# Elec_2013_Combined_v2.net
KiCad netlist of a schematic drawn in EAGLE
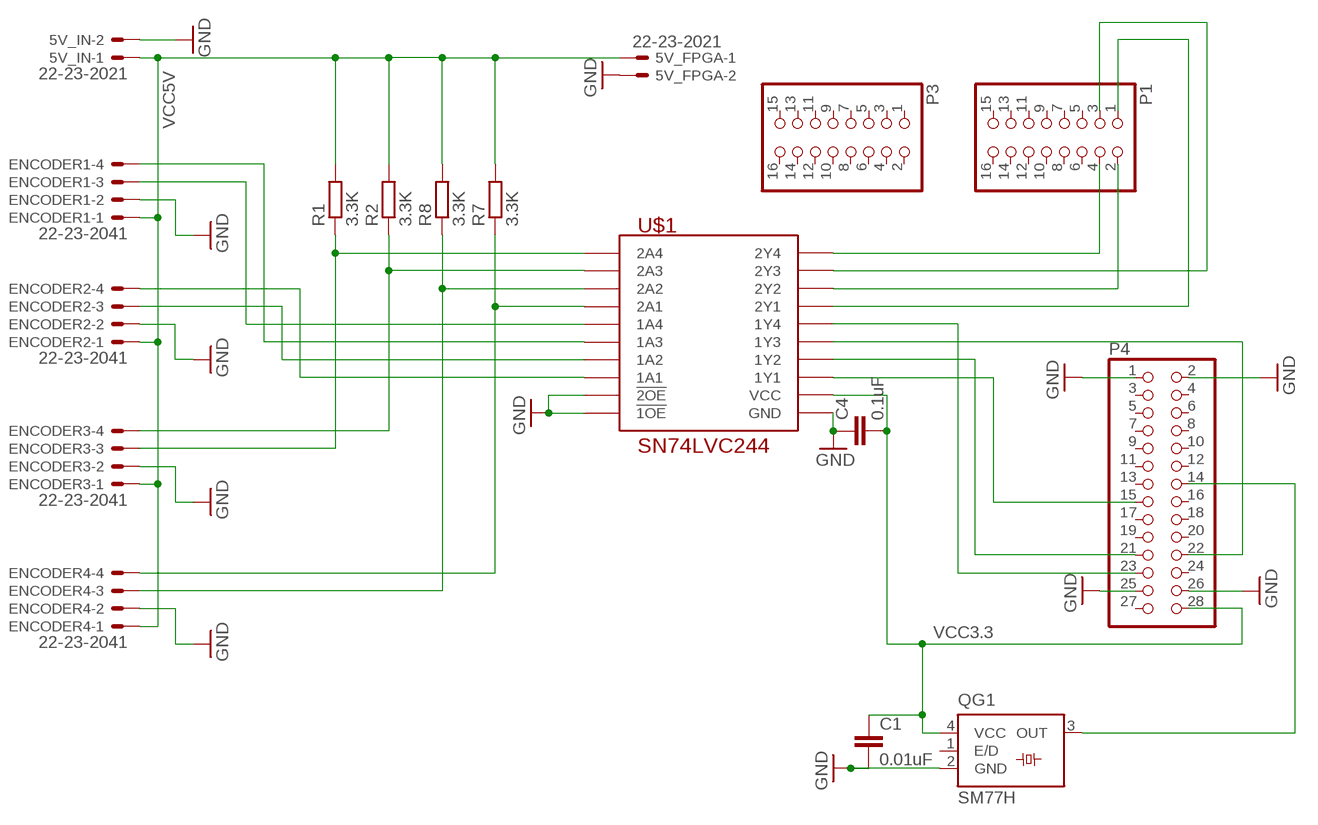
[diagram p0: schematic, sheet 1, part 1 of 2]
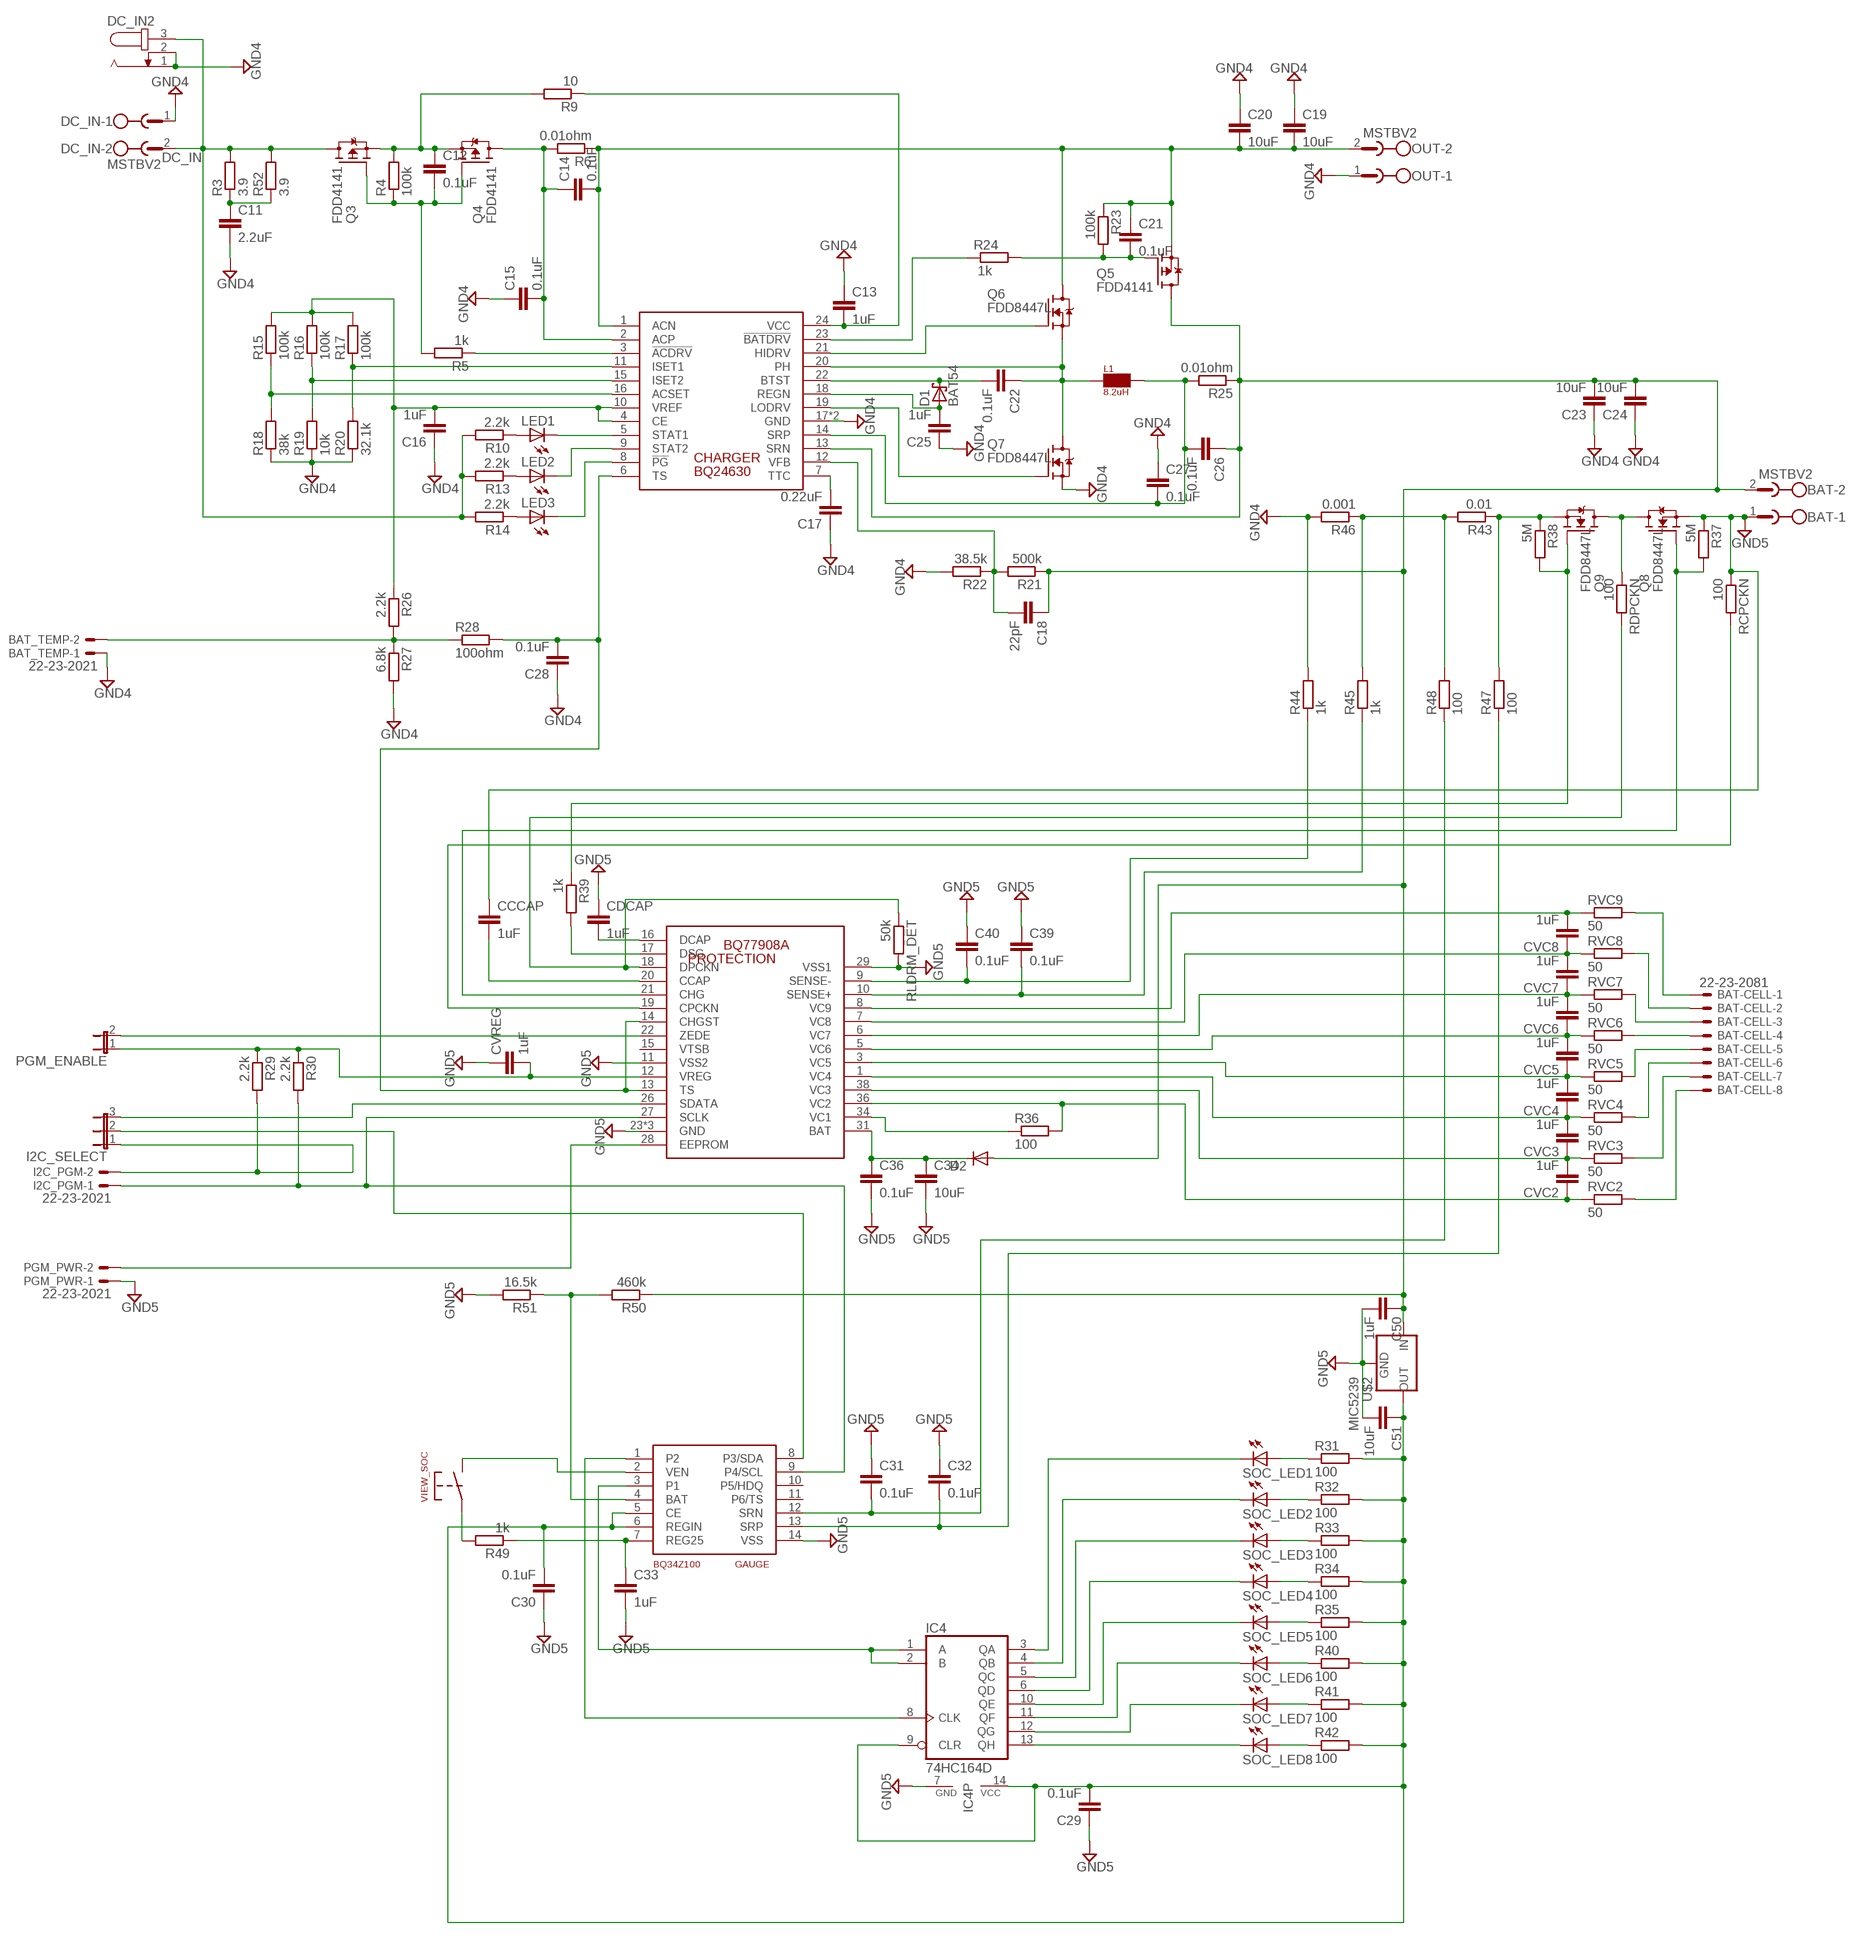
[diagram p1: schematic, sheet 1, part 2 of 2]

(export (version "E")
  (design (tool "Eeschema 10.0.6"))
  (components
    (comp (ref "5V_FPGA")
      (value "22-23-2021")
      (footprint "eagle-import:22-23-2021")
      (fields
        (field (name "MF") "MOLEX")
        (field (name "MF_1") "MOLEX")
        (field (name "MPN") "22-23-2021")
        (field (name "OC_FARNELL") "1462926")
        (field (name "OC_NEWARK") "25C3832")
      )
      (libsource (lib "eagle-import") (part "22-23-2021"))
    )
    (comp (ref "5V_IN")
      (value "22-23-2021")
      (footprint "eagle-import:22-23-2021")
      (fields (field (name "MF") "MOLEX"))
      (libsource (lib "eagle-import") (part "22-23-2021"))
    )
    (comp (ref "BAT")
      (value "MSTBV2")
      (footprint "eagle-import:MSTBV2")
      (fields
        (field (name "MPN") "MSTBV 2,5/2-GF-5.08")
        (field (name "MPN_1") "MSTBV 2,5/2-GF-5.08")
        (field (name "OC_FARNELL") "1792792")
        (field (name "OC_NEWARK") "69R9845")
      )
      (libsource (lib "eagle-import") (part "MSTBV2"))
    )
    (comp (ref "BAT-CELL")
      (value "22-23-2081")
      (footprint "eagle-import:22-23-2081")
      (fields (field (name "MF") "MOLEX"))
      (libsource (lib "eagle-import") (part "22-23-2081"))
    )
    (comp (ref "BAT_TEMP")
      (value "22-23-2021")
      (footprint "eagle-import:22-23-2021")
      (fields
        (field (name "MF") "MOLEX")
        (field (name "MF_1") "MOLEX")
        (field (name "MPN") "22-23-2021")
        (field (name "OC_FARNELL") "1462926")
        (field (name "OC_NEWARK") "25C3832")
      )
      (libsource (lib "eagle-import") (part "22-23-2021"))
    )
    (comp (ref "C1")
      (value "0.01uF")
      (footprint "eagle-import:C0603")
      (libsource (lib "eagle-import") (part "C-EUC0603"))
    )
    (comp (ref "C4")
      (value "0.1uF")
      (footprint "eagle-import:C0603")
      (libsource (lib "eagle-import") (part "C-EUC0603"))
    )
    (comp (ref "C11")
      (value "2.2uF")
      (footprint "eagle-import:C1206")
      (libsource (lib "eagle-import") (part "C-EUC1206"))
    )
    (comp (ref "C12")
      (value "0.1uF")
      (footprint "eagle-import:C0603")
      (libsource (lib "eagle-import") (part "C-EUC0603"))
    )
    (comp (ref "C13")
      (value "1uF")
      (footprint "eagle-import:C1206")
      (libsource (lib "eagle-import") (part "C-EUC1206"))
    )
    (comp (ref "C14")
      (value "0.1uF")
      (footprint "eagle-import:C0603")
      (libsource (lib "eagle-import") (part "C-EUC0603"))
    )
    (comp (ref "C15")
      (value "0.1uF")
      (footprint "eagle-import:C0603")
      (libsource (lib "eagle-import") (part "C-EUC0603"))
    )
    (comp (ref "C16")
      (value "1uF")
      (footprint "eagle-import:C0805")
      (libsource (lib "eagle-import") (part "C-EUC0805"))
    )
    (comp (ref "C17")
      (value "0.22uF")
      (footprint "eagle-import:C0603")
      (libsource (lib "eagle-import") (part "C-EUC0603"))
    )
    (comp (ref "C18")
      (value "22pF")
      (footprint "eagle-import:C0603")
      (libsource (lib "eagle-import") (part "C-EUC0603"))
    )
    (comp (ref "C19")
      (value "10uF")
      (footprint "eagle-import:C1812")
      (libsource (lib "eagle-import") (part "C-EUC1812"))
    )
    (comp (ref "C20")
      (value "10uF")
      (footprint "eagle-import:C1812")
      (libsource (lib "eagle-import") (part "C-EUC1812"))
    )
    (comp (ref "C21")
      (value "0.1uF")
      (footprint "eagle-import:C0603")
      (libsource (lib "eagle-import") (part "C-EUC0603"))
    )
    (comp (ref "C22")
      (value "0.1uF")
      (footprint "eagle-import:C0603")
      (libsource (lib "eagle-import") (part "C-EUC0603"))
    )
    (comp (ref "C23")
      (value "10uF")
      (footprint "eagle-import:C1812")
      (libsource (lib "eagle-import") (part "C-EUC1812"))
    )
    (comp (ref "C24")
      (value "10uF")
      (footprint "eagle-import:C1812")
      (libsource (lib "eagle-import") (part "C-EUC1812"))
    )
    (comp (ref "C25")
      (value "1uF")
      (footprint "eagle-import:C0805")
      (libsource (lib "eagle-import") (part "C-EUC0805"))
    )
    (comp (ref "C26")
      (value "0.1uF")
      (footprint "eagle-import:C0603")
      (libsource (lib "eagle-import") (part "C-EUC0603"))
    )
    (comp (ref "C27")
      (value "0.1uF")
      (footprint "eagle-import:C0603")
      (libsource (lib "eagle-import") (part "C-EUC0603"))
    )
    (comp (ref "C28")
      (value "0.1uF")
      (footprint "eagle-import:C0603")
      (libsource (lib "eagle-import") (part "C-EUC0603"))
    )
    (comp (ref "C29")
      (value "0.1uF")
      (footprint "eagle-import:C0603")
      (libsource (lib "eagle-import") (part "C-EUC0603"))
    )
    (comp (ref "C30")
      (value "0.1uF")
      (footprint "eagle-import:C0603")
      (libsource (lib "eagle-import") (part "C-EUC0603"))
    )
    (comp (ref "C31")
      (value "0.1uF")
      (footprint "eagle-import:C0603")
      (libsource (lib "eagle-import") (part "C-EUC0603"))
    )
    (comp (ref "C32")
      (value "0.1uF")
      (footprint "eagle-import:C0603")
      (libsource (lib "eagle-import") (part "C-EUC0603"))
    )
    (comp (ref "C33")
      (value "1uF")
      (footprint "eagle-import:C0603")
      (libsource (lib "eagle-import") (part "C-EUC0603"))
    )
    (comp (ref "C34")
      (value "10uF")
      (footprint "eagle-import:C1210")
      (libsource (lib "eagle-import") (part "C-EUC1210"))
    )
    (comp (ref "C36")
      (value "0.1uF")
      (footprint "eagle-import:C1210")
      (libsource (lib "eagle-import") (part "C-EUC1210"))
    )
    (comp (ref "C39")
      (value "0.1uF")
      (footprint "eagle-import:C0603")
      (libsource (lib "eagle-import") (part "C-EUC0603"))
    )
    (comp (ref "C40")
      (value "0.1uF")
      (footprint "eagle-import:C0603")
      (libsource (lib "eagle-import") (part "C-EUC0603"))
    )
    (comp (ref "C50")
      (value "1uF")
      (footprint "eagle-import:C0603")
      (libsource (lib "eagle-import") (part "C-EUC0603"))
    )
    (comp (ref "C51")
      (value "10uF")
      (footprint "eagle-import:C0603")
      (libsource (lib "eagle-import") (part "C-EUC0603"))
    )
    (comp (ref "CCCAP")
      (value "1uF")
      (footprint "eagle-import:C1206")
      (libsource (lib "eagle-import") (part "C-EUC1206"))
    )
    (comp (ref "CDCAP")
      (value "1uF")
      (footprint "eagle-import:C1206")
      (libsource (lib "eagle-import") (part "C-EUC1206"))
    )
    (comp (ref "CHARGER")
      (value "BQ24630")
      (footprint "eagle-import:QFN-24")
      (libsource (lib "eagle-import") (part "BQ24630"))
    )
    (comp (ref "CVC2")
      (value "1uF")
      (footprint "eagle-import:C0603")
      (libsource (lib "eagle-import") (part "C-EUC0603"))
    )
    (comp (ref "CVC3")
      (value "1uF")
      (footprint "eagle-import:C0603")
      (libsource (lib "eagle-import") (part "C-EUC0603"))
    )
    (comp (ref "CVC4")
      (value "1uF")
      (footprint "eagle-import:C0603")
      (libsource (lib "eagle-import") (part "C-EUC0603"))
    )
    (comp (ref "CVC5")
      (value "1uF")
      (footprint "eagle-import:C0603")
      (libsource (lib "eagle-import") (part "C-EUC0603"))
    )
    (comp (ref "CVC6")
      (value "1uF")
      (footprint "eagle-import:C0603")
      (libsource (lib "eagle-import") (part "C-EUC0603"))
    )
    (comp (ref "CVC7")
      (value "1uF")
      (footprint "eagle-import:C0603")
      (libsource (lib "eagle-import") (part "C-EUC0603"))
    )
    (comp (ref "CVC8")
      (value "1uF")
      (footprint "eagle-import:C0603")
      (libsource (lib "eagle-import") (part "C-EUC0603"))
    )
    (comp (ref "CVREG")
      (value "1uF")
      (footprint "eagle-import:C0603")
      (libsource (lib "eagle-import") (part "C-EUC0603"))
    )
    (comp (ref "D1")
      (value "BAT54")
      (footprint "eagle-import:SOT23")
      (libsource (lib "eagle-import") (part "BAT54"))
    )
    (comp (ref "D2")
      (value "DIODE-SOD123")
      (footprint "eagle-import:SOD123")
      (libsource (lib "eagle-import") (part "DIODE-SOD123"))
    )
    (comp (ref "DC_IN")
      (value "MSTBV2")
      (footprint "eagle-import:MSTBV2")
      (fields (field (name "MPN") "MSTBV 2,5/2-GF-5.08"))
      (libsource (lib "eagle-import") (part "MSTBV2"))
    )
    (comp (ref "DC_IN2")
      (value "JACK-PLUG1")
      (footprint "eagle-import:SPC4078")
      (libsource (lib "eagle-import") (part "JACK-PLUG1"))
    )
    (comp (ref "ENCODER1")
      (value "22-23-2041")
      (footprint "eagle-import:22-23-2041")
      (fields (field (name "MF") "MOLEX"))
      (libsource (lib "eagle-import") (part "22-23-2041"))
    )
    (comp (ref "ENCODER2")
      (value "22-23-2041")
      (footprint "eagle-import:22-23-2041")
      (fields (field (name "MF") "MOLEX"))
      (libsource (lib "eagle-import") (part "22-23-2041"))
    )
    (comp (ref "ENCODER3")
      (value "22-23-2041")
      (footprint "eagle-import:22-23-2041")
      (fields (field (name "MF") "MOLEX"))
      (libsource (lib "eagle-import") (part "22-23-2041"))
    )
    (comp (ref "ENCODER4")
      (value "22-23-2041")
      (footprint "eagle-import:22-23-2041")
      (fields (field (name "MF") "MOLEX"))
      (libsource (lib "eagle-import") (part "22-23-2041"))
    )
    (comp (ref "GAUGE")
      (value "BQ34Z100")
      (footprint "eagle-import:TSSOP-14-0.65MM")
      (libsource (lib "eagle-import") (part "BQ34Z100"))
    )
    (comp (ref "I2C_PGM")
      (value "22-23-2021")
      (footprint "eagle-import:22-23-2021")
      (fields
        (field (name "MF") "MOLEX")
        (field (name "MF_1") "MOLEX")
        (field (name "MPN") "22-23-2021")
        (field (name "OC_FARNELL") "1462926")
        (field (name "OC_NEWARK") "25C3832")
      )
      (libsource (lib "eagle-import") (part "22-23-2021"))
    )
    (comp (ref "I2C_SELECT")
      (value "JP2E")
      (footprint "eagle-import:JP2")
      (libsource (lib "eagle-import") (part "JP2E"))
    )
    (comp (ref "IC4")
      (value "74HC164D")
      (footprint "eagle-import:SO14")
      (libsource (lib "eagle-import") (part "74164DHC"))
    )
    (comp (ref "L1")
      (value "8.2uH")
      (footprint "eagle-import:5050CE")
      (libsource (lib "eagle-import") (part "IHLP-5050CE"))
    )
    (comp (ref "LED1")
      (value "LEDCHIP-LED0603")
      (footprint "eagle-import:CHIP-LED0603")
      (libsource (lib "eagle-import") (part "LEDCHIP-LED0603"))
    )
    (comp (ref "LED2")
      (value "LEDCHIP-LED0603")
      (footprint "eagle-import:CHIP-LED0603")
      (libsource (lib "eagle-import") (part "LEDCHIP-LED0603"))
    )
    (comp (ref "LED3")
      (value "LEDCHIP-LED0603")
      (footprint "eagle-import:CHIP-LED0603")
      (libsource (lib "eagle-import") (part "LEDCHIP-LED0603"))
    )
    (comp (ref "OUT")
      (value "MSTBV2")
      (footprint "eagle-import:MSTBV2")
      (fields
        (field (name "MPN") "MSTBV 2,5/2-GF-5.08")
        (field (name "MPN_1") "MSTBV 2,5/2-GF-5.08")
        (field (name "OC_FARNELL") "1792792")
        (field (name "OC_NEWARK") "69R9845")
      )
      (libsource (lib "eagle-import") (part "MSTBV2"))
    )
    (comp (ref "P1")
      (value "PINHD-2X8")
      (footprint "eagle-import:2X08")
      (libsource (lib "eagle-import") (part "PINHD-2X8"))
    )
    (comp (ref "P3")
      (value "PINHD-2X8")
      (footprint "eagle-import:2X08")
      (libsource (lib "eagle-import") (part "PINHD-2X8"))
    )
    (comp (ref "P4")
      (value "PINHD-2X14")
      (footprint "eagle-import:2X14")
      (libsource (lib "eagle-import") (part "PINHD-2X14"))
    )
    (comp (ref "PGM_ENABLE")
      (value "JP1E")
      (footprint "eagle-import:JP1")
      (libsource (lib "eagle-import") (part "JP1E"))
    )
    (comp (ref "PGM_PWR")
      (value "22-23-2021")
      (footprint "eagle-import:22-23-2021")
      (fields
        (field (name "MF") "MOLEX")
        (field (name "MF_1") "MOLEX")
        (field (name "MPN") "22-23-2021")
        (field (name "OC_FARNELL") "1462926")
        (field (name "OC_NEWARK") "25C3832")
      )
      (libsource (lib "eagle-import") (part "22-23-2021"))
    )
    (comp (ref "PROTECTION")
      (value "BQ77908A")
      (footprint "eagle-import:TSSOP-38-0.5MM")
      (libsource (lib "eagle-import") (part "BQ77908A"))
    )
    (comp (ref "Q3")
      (value "FDD4141")
      (footprint "eagle-import:TO252")
      (libsource (lib "eagle-import") (part "FDD4141TO252"))
    )
    (comp (ref "Q4")
      (value "FDD4141")
      (footprint "eagle-import:TO252")
      (libsource (lib "eagle-import") (part "FDD4141TO252"))
    )
    (comp (ref "Q5")
      (value "FDD4141")
      (footprint "eagle-import:TO252")
      (libsource (lib "eagle-import") (part "FDD4141TO252"))
    )
    (comp (ref "Q6")
      (value "FDD8447L")
      (footprint "eagle-import:TO252")
      (libsource (lib "eagle-import") (part "FDD8447L"))
    )
    (comp (ref "Q7")
      (value "FDD8447L")
      (footprint "eagle-import:TO252")
      (libsource (lib "eagle-import") (part "FDD8447L"))
    )
    (comp (ref "Q8")
      (value "FDD8447L")
      (footprint "eagle-import:TO252")
      (libsource (lib "eagle-import") (part "FDD8447L"))
    )
    (comp (ref "Q9")
      (value "FDD8447L")
      (footprint "eagle-import:TO252")
      (libsource (lib "eagle-import") (part "FDD8447L"))
    )
    (comp (ref "QG1")
      (value "SM77H")
      (footprint "eagle-import:SM77H")
      (libsource (lib "eagle-import") (part "SM77H"))
    )
    (comp (ref "R1")
      (value "3.3K")
      (footprint "eagle-import:R0603")
      (libsource (lib "eagle-import") (part "R-EU_R0603"))
    )
    (comp (ref "R2")
      (value "3.3K")
      (footprint "eagle-import:R0603")
      (libsource (lib "eagle-import") (part "R-EU_R0603"))
    )
    (comp (ref "R3")
      (value "3.9")
      (footprint "eagle-import:R1206")
      (libsource (lib "eagle-import") (part "R-EU_R1206"))
    )
    (comp (ref "R4")
      (value "100k")
      (footprint "eagle-import:R0603")
      (libsource (lib "eagle-import") (part "R-EU_R0603"))
    )
    (comp (ref "R5")
      (value "1k")
      (footprint "eagle-import:R0603")
      (libsource (lib "eagle-import") (part "R-EU_R0603"))
    )
    (comp (ref "R6")
      (value "0.01ohm")
      (footprint "eagle-import:R2010")
      (libsource (lib "eagle-import") (part "R-EU_R2010"))
    )
    (comp (ref "R7")
      (value "3.3K")
      (footprint "eagle-import:R0603")
      (libsource (lib "eagle-import") (part "R-EU_R0603"))
    )
    (comp (ref "R8")
      (value "3.3K")
      (footprint "eagle-import:R0603")
      (libsource (lib "eagle-import") (part "R-EU_R0603"))
    )
    (comp (ref "R9")
      (value "10")
      (footprint "eagle-import:R1206")
      (libsource (lib "eagle-import") (part "R-EU_R1206"))
    )
    (comp (ref "R10")
      (value "2.2k")
      (footprint "eagle-import:R0603")
      (libsource (lib "eagle-import") (part "R-EU_R0603"))
    )
    (comp (ref "R13")
      (value "2.2k")
      (footprint "eagle-import:R0603")
      (libsource (lib "eagle-import") (part "R-EU_R0603"))
    )
    (comp (ref "R14")
      (value "2.2k")
      (footprint "eagle-import:R0603")
      (libsource (lib "eagle-import") (part "R-EU_R0603"))
    )
    (comp (ref "R15")
      (value "100k")
      (footprint "eagle-import:R0805")
      (libsource (lib "eagle-import") (part "R-EU_R0805"))
    )
    (comp (ref "R16")
      (value "100k")
      (footprint "eagle-import:R0805")
      (libsource (lib "eagle-import") (part "R-EU_R0805"))
    )
    (comp (ref "R17")
      (value "100k")
      (footprint "eagle-import:R0805")
      (libsource (lib "eagle-import") (part "R-EU_R0805"))
    )
    (comp (ref "R18")
      (value "38k")
      (footprint "eagle-import:R0805")
      (libsource (lib "eagle-import") (part "R-EU_R0805"))
    )
    (comp (ref "R19")
      (value "10k")
      (footprint "eagle-import:R0805")
      (libsource (lib "eagle-import") (part "R-EU_R0805"))
    )
    (comp (ref "R20")
      (value "32.1k")
      (footprint "eagle-import:R0805")
      (libsource (lib "eagle-import") (part "R-EU_R0805"))
    )
    (comp (ref "R21")
      (value "500k")
      (footprint "eagle-import:R0805")
      (libsource (lib "eagle-import") (part "R-EU_R0805"))
    )
    (comp (ref "R22")
      (value "38.5k")
      (footprint "eagle-import:R0805")
      (libsource (lib "eagle-import") (part "R-EU_R0805"))
    )
    (comp (ref "R23")
      (value "100k")
      (footprint "eagle-import:R0603")
      (libsource (lib "eagle-import") (part "R-EU_R0603"))
    )
    (comp (ref "R24")
      (value "1k")
      (footprint "eagle-import:R0603")
      (libsource (lib "eagle-import") (part "R-EU_R0603"))
    )
    (comp (ref "R25")
      (value "0.01ohm")
      (footprint "eagle-import:R2010")
      (libsource (lib "eagle-import") (part "R-EU_R2010"))
    )
    (comp (ref "R26")
      (value "2.2k")
      (footprint "eagle-import:R0603")
      (libsource (lib "eagle-import") (part "R-EU_R0603"))
    )
    (comp (ref "R27")
      (value "6.8k")
      (footprint "eagle-import:R0603")
      (libsource (lib "eagle-import") (part "R-EU_R0603"))
    )
    (comp (ref "R28")
      (value "100ohm")
      (footprint "eagle-import:R0603")
      (libsource (lib "eagle-import") (part "R-EU_R0603"))
    )
    (comp (ref "R29")
      (value "2.2k")
      (footprint "eagle-import:R0603")
      (libsource (lib "eagle-import") (part "R-EU_R0603"))
    )
    (comp (ref "R30")
      (value "2.2k")
      (footprint "eagle-import:R0603")
      (libsource (lib "eagle-import") (part "R-EU_R0603"))
    )
    (comp (ref "R31")
      (value "100")
      (footprint "eagle-import:R0603")
      (libsource (lib "eagle-import") (part "R-EU_R0603"))
    )
    (comp (ref "R32")
      (value "100")
      (footprint "eagle-import:R0603")
      (libsource (lib "eagle-import") (part "R-EU_R0603"))
    )
    (comp (ref "R33")
      (value "100")
      (footprint "eagle-import:R0603")
      (libsource (lib "eagle-import") (part "R-EU_R0603"))
    )
    (comp (ref "R34")
      (value "100")
      (footprint "eagle-import:R0603")
      (libsource (lib "eagle-import") (part "R-EU_R0603"))
    )
    (comp (ref "R35")
      (value "100")
      (footprint "eagle-import:R0603")
      (libsource (lib "eagle-import") (part "R-EU_R0603"))
    )
    (comp (ref "R36")
      (value "100")
      (footprint "eagle-import:R0603")
      (libsource (lib "eagle-import") (part "R-EU_R0603"))
    )
    (comp (ref "R37")
      (value "5M")
      (footprint "eagle-import:R0603")
      (libsource (lib "eagle-import") (part "R-EU_R0603"))
    )
    (comp (ref "R38")
      (value "5M")
      (footprint "eagle-import:R0603")
      (libsource (lib "eagle-import") (part "R-EU_R0603"))
    )
    (comp (ref "R39")
      (value "1k")
      (footprint "eagle-import:R0603")
      (libsource (lib "eagle-import") (part "R-EU_R0603"))
    )
    (comp (ref "R40")
      (value "100")
      (footprint "eagle-import:R0603")
      (libsource (lib "eagle-import") (part "R-EU_R0603"))
    )
    (comp (ref "R41")
      (value "100")
      (footprint "eagle-import:R0603")
      (libsource (lib "eagle-import") (part "R-EU_R0603"))
    )
    (comp (ref "R42")
      (value "100")
      (footprint "eagle-import:R0603")
      (libsource (lib "eagle-import") (part "R-EU_R0603"))
    )
    (comp (ref "R43")
      (value "0.01")
      (footprint "eagle-import:R2010")
      (libsource (lib "eagle-import") (part "R-EU_R2010"))
    )
    (comp (ref "R44")
      (value "1k")
      (footprint "eagle-import:R0603")
      (libsource (lib "eagle-import") (part "R-EU_R0603"))
    )
    (comp (ref "R45")
      (value "1k")
      (footprint "eagle-import:R0603")
      (libsource (lib "eagle-import") (part "R-EU_R0603"))
    )
    (comp (ref "R46")
      (value "0.001")
      (footprint "eagle-import:R2010")
      (libsource (lib "eagle-import") (part "R-EU_R2010"))
    )
    (comp (ref "R47")
      (value "100")
      (footprint "eagle-import:R0603")
      (libsource (lib "eagle-import") (part "R-EU_R0603"))
    )
    (comp (ref "R48")
      (value "100")
      (footprint "eagle-import:R0603")
      (libsource (lib "eagle-import") (part "R-EU_R0603"))
    )
    (comp (ref "R49")
      (value "1k")
      (footprint "eagle-import:R0603")
      (libsource (lib "eagle-import") (part "R-EU_R0603"))
    )
    (comp (ref "R50")
      (value "460k")
      (footprint "eagle-import:R0805")
      (libsource (lib "eagle-import") (part "R-EU_R0805"))
    )
    (comp (ref "R51")
      (value "16.5k")
      (footprint "eagle-import:R0603")
      (libsource (lib "eagle-import") (part "R-EU_R0603"))
    )
    (comp (ref "R52")
      (value "3.9")
      (footprint "eagle-import:R1206")
      (libsource (lib "eagle-import") (part "R-EU_R1206"))
    )
    (comp (ref "RCPCKN")
      (value "100")
      (footprint "eagle-import:R0603")
      (libsource (lib "eagle-import") (part "R-EU_R0603"))
    )
    (comp (ref "RDPCKN")
      (value "100")
      (footprint "eagle-import:R0603")
      (libsource (lib "eagle-import") (part "R-EU_R0603"))
    )
    (comp (ref "RLDRM_DET")
      (value "50k")
      (footprint "eagle-import:R0603")
      (libsource (lib "eagle-import") (part "R-EU_R0603"))
    )
    (comp (ref "RVC2")
      (value "50")
      (footprint "eagle-import:R1206")
      (libsource (lib "eagle-import") (part "R-EU_R1206"))
    )
    (comp (ref "RVC3")
      (value "50")
      (footprint "eagle-import:R1206")
      (libsource (lib "eagle-import") (part "R-EU_R1206"))
    )
    (comp (ref "RVC4")
      (value "50")
      (footprint "eagle-import:R1206")
      (libsource (lib "eagle-import") (part "R-EU_R1206"))
    )
    (comp (ref "RVC5")
      (value "50")
      (footprint "eagle-import:R1206")
      (libsource (lib "eagle-import") (part "R-EU_R1206"))
    )
    (comp (ref "RVC6")
      (value "50")
      (footprint "eagle-import:R1206")
      (libsource (lib "eagle-import") (part "R-EU_R1206"))
    )
    (comp (ref "RVC7")
      (value "50")
      (footprint "eagle-import:R1206")
      (libsource (lib "eagle-import") (part "R-EU_R1206"))
    )
    (comp (ref "RVC8")
      (value "50")
      (footprint "eagle-import:R1206")
      (libsource (lib "eagle-import") (part "R-EU_R1206"))
    )
    (comp (ref "RVC9")
      (value "50")
      (footprint "eagle-import:R1206")
      (libsource (lib "eagle-import") (part "R-EU_R1206"))
    )
    (comp (ref "SOC_LED1")
      (value "LEDCHIP-LED0603")
      (footprint "eagle-import:CHIP-LED0603")
      (libsource (lib "eagle-import") (part "LEDCHIP-LED0603"))
    )
    (comp (ref "SOC_LED2")
      (value "LEDCHIP-LED0603")
      (footprint "eagle-import:CHIP-LED0603")
      (libsource (lib "eagle-import") (part "LEDCHIP-LED0603"))
    )
    (comp (ref "SOC_LED3")
      (value "LEDCHIP-LED0603")
      (footprint "eagle-import:CHIP-LED0603")
      (libsource (lib "eagle-import") (part "LEDCHIP-LED0603"))
    )
    (comp (ref "SOC_LED4")
      (value "LEDCHIP-LED0603")
      (footprint "eagle-import:CHIP-LED0603")
      (libsource (lib "eagle-import") (part "LEDCHIP-LED0603"))
    )
    (comp (ref "SOC_LED5")
      (value "LEDCHIP-LED0603")
      (footprint "eagle-import:CHIP-LED0603")
      (libsource (lib "eagle-import") (part "LEDCHIP-LED0603"))
    )
    (comp (ref "SOC_LED6")
      (value "LEDCHIP-LED0603")
      (footprint "eagle-import:CHIP-LED0603")
      (libsource (lib "eagle-import") (part "LEDCHIP-LED0603"))
    )
    (comp (ref "SOC_LED7")
      (value "LEDCHIP-LED0603")
      (footprint "eagle-import:CHIP-LED0603")
      (libsource (lib "eagle-import") (part "LEDCHIP-LED0603"))
    )
    (comp (ref "SOC_LED8")
      (value "LEDCHIP-LED0603")
      (footprint "eagle-import:CHIP-LED0603")
      (libsource (lib "eagle-import") (part "LEDCHIP-LED0603"))
    )
    (comp (ref "U$1")
      (value "SN74LVC244")
      (footprint "eagle-import:TSSOP-20-0.65MM")
      (libsource (lib "eagle-import") (part "SN74LVC244"))
    )
    (comp (ref "U$2")
      (value "MIC5239")
      (footprint "eagle-import:SOT223")
      (libsource (lib "eagle-import") (part "MIC5239"))
    )
    (comp (ref "VIEW_SOC")
      (value "PUSHBUTTON")
      (footprint "eagle-import:PUSHBUTTON")
      (libsource (lib "eagle-import") (part "PUSHBUTTON"))
    )
  )
  (nets
    (net (code "1") (name "/DC_IN") (class "Default")
      (node (ref "DC_IN") (pin "2") (pinfunction "1_2") (pintype "passive"))
      (node (ref "DC_IN2") (pin "3") (pinfunction "3_3") (pintype "passive"))
      (node (ref "Q3") (pin "3") (pinfunction "D_3") (pintype "passive"))
      (node (ref "R10") (pin "2") (pinfunction "2_2") (pintype "passive"))
      (node (ref "R13") (pin "2") (pinfunction "2_2") (pintype "passive"))
      (node (ref "R14") (pin "2") (pinfunction "2_2") (pintype "passive"))
      (node (ref "R3") (pin "2") (pinfunction "2_2") (pintype "passive"))
      (node (ref "R52") (pin "2") (pinfunction "2_2") (pintype "passive"))
    )
    (net (code "2") (name "/VCC3.3") (class "Default")
      (node (ref "C1") (pin "1") (pinfunction "1_1") (pintype "passive"))
      (node (ref "C4") (pin "2") (pinfunction "2_2") (pintype "passive"))
      (node (ref "P4") (pin "28") (pinfunction "28_28") (pintype "passive"))
      (node (ref "QG1") (pin "4") (pinfunction "VCC_4") (pintype "power_in"))
      (node (ref "U$1") (pin "P$20") (pinfunction "VCC_P$20") (pintype "bidirectional"))
    )
    (net (code "3") (name "/VCC5V") (class "Default")
      (node (ref "5V_FPGA") (pin "1") (pinfunction "S_1") (pintype "passive"))
      (node (ref "5V_IN") (pin "1") (pinfunction "S_1") (pintype "passive"))
      (node (ref "ENCODER1") (pin "1") (pinfunction "S_1") (pintype "passive"))
      (node (ref "ENCODER2") (pin "1") (pinfunction "S_1") (pintype "passive"))
      (node (ref "ENCODER3") (pin "1") (pinfunction "S_1") (pintype "passive"))
      (node (ref "ENCODER4") (pin "1") (pinfunction "S_1") (pintype "passive"))
      (node (ref "R1") (pin "2") (pinfunction "2_2") (pintype "passive"))
      (node (ref "R2") (pin "2") (pinfunction "2_2") (pintype "passive"))
      (node (ref "R7") (pin "2") (pinfunction "2_2") (pintype "passive"))
      (node (ref "R8") (pin "2") (pinfunction "2_2") (pintype "passive"))
    )
    (net (code "4") (name "GND") (class "Default")
      (node (ref "5V_FPGA") (pin "2") (pinfunction "S_2") (pintype "passive"))
      (node (ref "5V_IN") (pin "2") (pinfunction "S_2") (pintype "passive"))
      (node (ref "C1") (pin "2") (pinfunction "2_2") (pintype "passive"))
      (node (ref "C4") (pin "1") (pinfunction "1_1") (pintype "passive"))
      (node (ref "ENCODER1") (pin "2") (pinfunction "S_2") (pintype "passive"))
      (node (ref "ENCODER2") (pin "2") (pinfunction "S_2") (pintype "passive"))
      (node (ref "ENCODER3") (pin "2") (pinfunction "S_2") (pintype "passive"))
      (node (ref "ENCODER4") (pin "2") (pinfunction "S_2") (pintype "passive"))
      (node (ref "P4") (pin "1") (pinfunction "1_1") (pintype "passive"))
      (node (ref "P4") (pin "2") (pinfunction "2_2") (pintype "passive"))
      (node (ref "P4") (pin "25") (pinfunction "25_25") (pintype "passive"))
      (node (ref "P4") (pin "26") (pinfunction "26_26") (pintype "passive"))
      (node (ref "QG1") (pin "2") (pinfunction "GND_2") (pintype "power_in"))
      (node (ref "U$1") (pin "P$1") (pinfunction "~{1OE}_P$1") (pintype "bidirectional"))
      (node (ref "U$1") (pin "P$10") (pinfunction "GND_P$10") (pintype "bidirectional"))
      (node (ref "U$1") (pin "P$19") (pinfunction "~{2OE}_P$19") (pintype "bidirectional"))
    )
    (net (code "5") (name "GND4") (class "Default")
      (node (ref "BAT_TEMP") (pin "1") (pinfunction "S_1") (pintype "passive"))
      (node (ref "C11") (pin "2") (pinfunction "2_2") (pintype "passive"))
      (node (ref "C13") (pin "1") (pinfunction "1_1") (pintype "passive"))
      (node (ref "C15") (pin "1") (pinfunction "1_1") (pintype "passive"))
      (node (ref "C16") (pin "1") (pinfunction "1_1") (pintype "passive"))
      (node (ref "C17") (pin "1") (pinfunction "1_1") (pintype "passive"))
      (node (ref "C19") (pin "1") (pinfunction "1_1") (pintype "passive"))
      (node (ref "C20") (pin "1") (pinfunction "1_1") (pintype "passive"))
      (node (ref "C23") (pin "1") (pinfunction "1_1") (pintype "passive"))
      (node (ref "C24") (pin "1") (pinfunction "1_1") (pintype "passive"))
      (node (ref "C25") (pin "1") (pinfunction "1_1") (pintype "passive"))
      (node (ref "C27") (pin "1") (pinfunction "1_1") (pintype "passive"))
      (node (ref "C28") (pin "1") (pinfunction "1_1") (pintype "passive"))
      (node (ref "CHARGER") (pin "17") (pinfunction "GND_17") (pintype "bidirectional"))
      (node (ref "CHARGER") (pin "THERMAL") (pinfunction "GND_THERMAL") (pintype "bidirectional"))
      (node (ref "DC_IN") (pin "1") (pinfunction "1_1") (pintype "passive"))
      (node (ref "DC_IN2") (pin "1") (pinfunction "1_1") (pintype "passive"))
      (node (ref "DC_IN2") (pin "2") (pinfunction "2_2") (pintype "passive"))
      (node (ref "OUT") (pin "1") (pinfunction "1_1") (pintype "passive"))
      (node (ref "Q7") (pin "2") (pinfunction "S_2") (pintype "passive"))
      (node (ref "R18") (pin "1") (pinfunction "1_1") (pintype "passive"))
      (node (ref "R19") (pin "1") (pinfunction "1_1") (pintype "passive"))
      (node (ref "R20") (pin "1") (pinfunction "1_1") (pintype "passive"))
      (node (ref "R22") (pin "2") (pinfunction "2_2") (pintype "passive"))
      (node (ref "R27") (pin "2") (pinfunction "2_2") (pintype "passive"))
      (node (ref "R44") (pin "2") (pinfunction "2_2") (pintype "passive"))
      (node (ref "R46") (pin "2") (pinfunction "2_2") (pintype "passive"))
    )
    (net (code "6") (name "GND5") (class "Default")
      (node (ref "BAT") (pin "1") (pinfunction "1_1") (pintype "passive"))
      (node (ref "C29") (pin "1") (pinfunction "1_1") (pintype "passive"))
      (node (ref "C30") (pin "1") (pinfunction "1_1") (pintype "passive"))
      (node (ref "C31") (pin "1") (pinfunction "1_1") (pintype "passive"))
      (node (ref "C32") (pin "1") (pinfunction "1_1") (pintype "passive"))
      (node (ref "C33") (pin "2") (pinfunction "2_2") (pintype "passive"))
      (node (ref "C34") (pin "2") (pinfunction "2_2") (pintype "passive"))
      (node (ref "C36") (pin "2") (pinfunction "2_2") (pintype "passive"))
      (node (ref "C39") (pin "1") (pinfunction "1_1") (pintype "passive"))
      (node (ref "C40") (pin "1") (pinfunction "1_1") (pintype "passive"))
      (node (ref "C50") (pin "2") (pinfunction "2_2") (pintype "passive"))
      (node (ref "C51") (pin "2") (pinfunction "2_2") (pintype "passive"))
      (node (ref "CCCAP") (pin "1") (pinfunction "1_1") (pintype "passive"))
      (node (ref "CDCAP") (pin "1") (pinfunction "1_1") (pintype "passive"))
      (node (ref "CVREG") (pin "1") (pinfunction "1_1") (pintype "passive"))
      (node (ref "GAUGE") (pin "14") (pinfunction "VSS_14") (pintype "bidirectional"))
      (node (ref "IC4") (pin "7") (pinfunction "GND_7") (pintype "power_in"))
      (node (ref "PGM_PWR") (pin "1") (pinfunction "S_1") (pintype "passive"))
      (node (ref "PROTECTION") (pin "11") (pinfunction "VSS2_11") (pintype "bidirectional"))
      (node (ref "PROTECTION") (pin "23") (pinfunction "GND_23") (pintype "bidirectional"))
      (node (ref "PROTECTION") (pin "24") (pinfunction "GND_24") (pintype "bidirectional"))
      (node (ref "PROTECTION") (pin "25") (pinfunction "GND_25") (pintype "bidirectional"))
      (node (ref "PROTECTION") (pin "29") (pinfunction "VSS1_29") (pintype "bidirectional"))
      (node (ref "Q8") (pin "2") (pinfunction "S_2") (pintype "passive"))
      (node (ref "R37") (pin "1") (pinfunction "1_1") (pintype "passive"))
      (node (ref "R51") (pin "2") (pinfunction "2_2") (pintype "passive"))
      (node (ref "RCPCKN") (pin "1") (pinfunction "1_1") (pintype "passive"))
      (node (ref "RLDRM_DET") (pin "2") (pinfunction "2_2") (pintype "passive"))
      (node (ref "U$2") (pin "2") (pinfunction "GND_2") (pintype "input"))
      (node (ref "U$2") (pin "4") (pinfunction "GND_4") (pintype "input"))
    )
    (net (code "7") (name "Net-(BAT-CELLA-S)") (class "Default")
      (node (ref "BAT-CELL") (pin "1") (pinfunction "S_1") (pintype "passive"))
      (node (ref "RVC9") (pin "2") (pinfunction "2_2") (pintype "passive"))
    )
    (net (code "8") (name "Net-(BAT-CELLB-S)") (class "Default")
      (node (ref "BAT-CELL") (pin "2") (pinfunction "S_2") (pintype "passive"))
      (node (ref "RVC8") (pin "2") (pinfunction "2_2") (pintype "passive"))
    )
    (net (code "9") (name "Net-(BAT-CELLC-S)") (class "Default")
      (node (ref "BAT-CELL") (pin "3") (pinfunction "S_3") (pintype "passive"))
      (node (ref "RVC7") (pin "2") (pinfunction "2_2") (pintype "passive"))
    )
    (net (code "10") (name "Net-(BAT-CELLD-S)") (class "Default")
      (node (ref "BAT-CELL") (pin "4") (pinfunction "S_4") (pintype "passive"))
      (node (ref "RVC6") (pin "2") (pinfunction "2_2") (pintype "passive"))
    )
    (net (code "11") (name "Net-(BAT-CELLE-S)") (class "Default")
      (node (ref "BAT-CELL") (pin "5") (pinfunction "S_5") (pintype "passive"))
      (node (ref "RVC5") (pin "2") (pinfunction "2_2") (pintype "passive"))
    )
    (net (code "12") (name "Net-(BAT-CELLF-S)") (class "Default")
      (node (ref "BAT-CELL") (pin "6") (pinfunction "S_6") (pintype "passive"))
      (node (ref "RVC4") (pin "2") (pinfunction "2_2") (pintype "passive"))
    )
    (net (code "13") (name "Net-(BAT-CELLG-S)") (class "Default")
      (node (ref "BAT-CELL") (pin "7") (pinfunction "S_7") (pintype "passive"))
      (node (ref "RVC3") (pin "2") (pinfunction "2_2") (pintype "passive"))
    )
    (net (code "14") (name "Net-(BAT-CELLH-S)") (class "Default")
      (node (ref "BAT-CELL") (pin "8") (pinfunction "S_8") (pintype "passive"))
      (node (ref "RVC2") (pin "2") (pinfunction "2_2") (pintype "passive"))
    )
    (net (code "15") (name "Net-(BATB-1)") (class "Default")
      (node (ref "BAT") (pin "2") (pinfunction "1_2") (pintype "passive"))
      (node (ref "C18") (pin "1") (pinfunction "1_1") (pintype "passive"))
      (node (ref "C23") (pin "2") (pinfunction "2_2") (pintype "passive"))
      (node (ref "C24") (pin "2") (pinfunction "2_2") (pintype "passive"))
      (node (ref "C26") (pin "1") (pinfunction "1_1") (pintype "passive"))
      (node (ref "C50") (pin "1") (pinfunction "1_1") (pintype "passive"))
      (node (ref "CHARGER") (pin "13") (pinfunction "SRN_13") (pintype "bidirectional"))
      (node (ref "D2") (pin "A") (pinfunction "A_A") (pintype "passive"))
      (node (ref "Q5") (pin "3") (pinfunction "D_3") (pintype "passive"))
      (node (ref "R21") (pin "1") (pinfunction "1_1") (pintype "passive"))
      (node (ref "R25") (pin "1") (pinfunction "1_1") (pintype "passive"))
      (node (ref "R50") (pin "1") (pinfunction "1_1") (pintype "passive"))
      (node (ref "U$2") (pin "1") (pinfunction "IN_1") (pintype "input"))
    )
    (net (code "16") (name "Net-(BAT_TEMPB-S)") (class "Default")
      (node (ref "BAT_TEMP") (pin "2") (pinfunction "S_2") (pintype "passive"))
      (node (ref "R26") (pin "2") (pinfunction "2_2") (pintype "passive"))
      (node (ref "R27") (pin "1") (pinfunction "1_1") (pintype "passive"))
      (node (ref "R28") (pin "1") (pinfunction "1_1") (pintype "passive"))
    )
    (net (code "17") (name "Net-(C11-Pad1)") (class "Default")
      (node (ref "C11") (pin "1") (pinfunction "1_1") (pintype "passive"))
      (node (ref "R3") (pin "1") (pinfunction "1_1") (pintype "passive"))
      (node (ref "R52") (pin "1") (pinfunction "1_1") (pintype "passive"))
    )
    (net (code "18") (name "Net-(CHARGER-ACN)") (class "Default")
      (node (ref "C14") (pin "2") (pinfunction "2_2") (pintype "passive"))
      (node (ref "C19") (pin "2") (pinfunction "2_2") (pintype "passive"))
      (node (ref "C20") (pin "2") (pinfunction "2_2") (pintype "passive"))
      (node (ref "C21") (pin "1") (pinfunction "1_1") (pintype "passive"))
      (node (ref "CHARGER") (pin "1") (pinfunction "ACN_1") (pintype "bidirectional"))
      (node (ref "OUT") (pin "2") (pinfunction "1_2") (pintype "passive"))
      (node (ref "Q5") (pin "2") (pinfunction "S_2") (pintype "passive"))
      (node (ref "Q6") (pin "3") (pinfunction "D_3") (pintype "passive"))
      (node (ref "R23") (pin "1") (pinfunction "1_1") (pintype "passive"))
      (node (ref "R6") (pin "1") (pinfunction "1_1") (pintype "passive"))
    )
    (net (code "19") (name "Net-(CHARGER-ACP)") (class "Default")
      (node (ref "C14") (pin "1") (pinfunction "1_1") (pintype "passive"))
      (node (ref "C15") (pin "2") (pinfunction "2_2") (pintype "passive"))
      (node (ref "CHARGER") (pin "2") (pinfunction "ACP_2") (pintype "bidirectional"))
      (node (ref "Q4") (pin "3") (pinfunction "D_3") (pintype "passive"))
      (node (ref "R6") (pin "2") (pinfunction "2_2") (pintype "passive"))
    )
    (net (code "20") (name "Net-(CHARGER-ACSET)") (class "Default")
      (node (ref "CHARGER") (pin "16") (pinfunction "ACSET_16") (pintype "bidirectional"))
      (node (ref "R15") (pin "1") (pinfunction "1_1") (pintype "passive"))
      (node (ref "R18") (pin "2") (pinfunction "2_2") (pintype "passive"))
    )
    (net (code "21") (name "Net-(CHARGER-BTST)") (class "Default")
      (node (ref "C22") (pin "2") (pinfunction "2_2") (pintype "passive"))
      (node (ref "CHARGER") (pin "22") (pinfunction "BTST_22") (pintype "bidirectional"))
      (node (ref "D1") (pin "3") (pinfunction "C_3") (pintype "passive"))
    )
    (net (code "22") (name "Net-(CHARGER-CE)") (class "Default")
      (node (ref "C16") (pin "2") (pinfunction "2_2") (pintype "passive"))
      (node (ref "CHARGER") (pin "10") (pinfunction "VREF_10") (pintype "bidirectional"))
      (node (ref "CHARGER") (pin "4") (pinfunction "CE_4") (pintype "bidirectional"))
      (node (ref "R15") (pin "2") (pinfunction "2_2") (pintype "passive"))
      (node (ref "R16") (pin "2") (pinfunction "2_2") (pintype "passive"))
      (node (ref "R17") (pin "2") (pinfunction "2_2") (pintype "passive"))
      (node (ref "R26") (pin "1") (pinfunction "1_1") (pintype "passive"))
    )
    (net (code "23") (name "Net-(CHARGER-HIDRV)") (class "Default")
      (node (ref "CHARGER") (pin "21") (pinfunction "HIDRV_21") (pintype "bidirectional"))
      (node (ref "Q6") (pin "1") (pinfunction "G_1") (pintype "passive"))
    )
    (net (code "24") (name "Net-(CHARGER-ISET1)") (class "Default")
      (node (ref "CHARGER") (pin "11") (pinfunction "ISET1_11") (pintype "bidirectional"))
      (node (ref "R17") (pin "1") (pinfunction "1_1") (pintype "passive"))
      (node (ref "R20") (pin "2") (pinfunction "2_2") (pintype "passive"))
    )
    (net (code "25") (name "Net-(CHARGER-ISET2)") (class "Default")
      (node (ref "CHARGER") (pin "15") (pinfunction "ISET2_15") (pintype "bidirectional"))
      (node (ref "R16") (pin "1") (pinfunction "1_1") (pintype "passive"))
      (node (ref "R19") (pin "2") (pinfunction "2_2") (pintype "passive"))
    )
    (net (code "26") (name "Net-(CHARGER-LODRV)") (class "Default")
      (node (ref "CHARGER") (pin "19") (pinfunction "LODRV_19") (pintype "bidirectional"))
      (node (ref "Q7") (pin "1") (pinfunction "G_1") (pintype "passive"))
    )
    (net (code "27") (name "Net-(CHARGER-PH)") (class "Default")
      (node (ref "C22") (pin "1") (pinfunction "1_1") (pintype "passive"))
      (node (ref "CHARGER") (pin "20") (pinfunction "PH_20") (pintype "bidirectional"))
      (node (ref "L1") (pin "P$1") (pinfunction "P$1_P$1") (pintype "bidirectional"))
      (node (ref "Q6") (pin "2") (pinfunction "S_2") (pintype "passive"))
      (node (ref "Q7") (pin "3") (pinfunction "D_3") (pintype "passive"))
    )
    (net (code "28") (name "Net-(CHARGER-REGN)") (class "Default")
      (node (ref "C25") (pin "2") (pinfunction "2_2") (pintype "passive"))
      (node (ref "CHARGER") (pin "18") (pinfunction "REGN_18") (pintype "bidirectional"))
      (node (ref "D1") (pin "1") (pinfunction "A_1") (pintype "passive"))
    )
    (net (code "29") (name "Net-(CHARGER-SRP)") (class "Default")
      (node (ref "C26") (pin "2") (pinfunction "2_2") (pintype "passive"))
      (node (ref "C27") (pin "2") (pinfunction "2_2") (pintype "passive"))
      (node (ref "CHARGER") (pin "14") (pinfunction "SRP_14") (pintype "bidirectional"))
      (node (ref "L1") (pin "P$2") (pinfunction "P$2_P$2") (pintype "bidirectional"))
      (node (ref "R25") (pin "2") (pinfunction "2_2") (pintype "passive"))
    )
    (net (code "30") (name "Net-(CHARGER-STAT1)") (class "Default")
      (node (ref "CHARGER") (pin "5") (pinfunction "STAT1_5") (pintype "bidirectional"))
      (node (ref "LED1") (pin "C") (pinfunction "C_C") (pintype "passive"))
    )
    (net (code "31") (name "Net-(CHARGER-STAT2)") (class "Default")
      (node (ref "CHARGER") (pin "9") (pinfunction "STAT2_9") (pintype "bidirectional"))
      (node (ref "LED2") (pin "C") (pinfunction "C_C") (pintype "passive"))
    )
    (net (code "32") (name "Net-(CHARGER-TS)") (class "Default")
      (node (ref "C28") (pin "2") (pinfunction "2_2") (pintype "passive"))
      (node (ref "CHARGER") (pin "6") (pinfunction "TS_6") (pintype "bidirectional"))
      (node (ref "PROTECTION") (pin "13") (pinfunction "TS_13") (pintype "bidirectional"))
      (node (ref "PROTECTION") (pin "14") (pinfunction "CHGST_14") (pintype "bidirectional"))
      (node (ref "R28") (pin "2") (pinfunction "2_2") (pintype "passive"))
    )
    (net (code "33") (name "Net-(CHARGER-TTC)") (class "Default")
      (node (ref "C17") (pin "2") (pinfunction "2_2") (pintype "passive"))
      (node (ref "CHARGER") (pin "7") (pinfunction "TTC_7") (pintype "bidirectional"))
    )
    (net (code "34") (name "Net-(CHARGER-VCC)") (class "Default")
      (node (ref "C13") (pin "2") (pinfunction "2_2") (pintype "passive"))
      (node (ref "CHARGER") (pin "24") (pinfunction "VCC_24") (pintype "bidirectional"))
      (node (ref "R9") (pin "1") (pinfunction "1_1") (pintype "passive"))
    )
    (net (code "35") (name "Net-(CHARGER-VFB)") (class "Default")
      (node (ref "C18") (pin "2") (pinfunction "2_2") (pintype "passive"))
      (node (ref "CHARGER") (pin "12") (pinfunction "VFB_12") (pintype "bidirectional"))
      (node (ref "R21") (pin "2") (pinfunction "2_2") (pintype "passive"))
      (node (ref "R22") (pin "1") (pinfunction "1_1") (pintype "passive"))
    )
    (net (code "36") (name "Net-(CHARGER-~{ACDRV})") (class "Default")
      (node (ref "CHARGER") (pin "3") (pinfunction "~{ACDRV}_3") (pintype "bidirectional"))
      (node (ref "R5") (pin "1") (pinfunction "1_1") (pintype "passive"))
    )
    (net (code "37") (name "Net-(CHARGER-~{BATDRV})") (class "Default")
      (node (ref "CHARGER") (pin "23") (pinfunction "~{BATDRV}_23") (pintype "bidirectional"))
      (node (ref "R24") (pin "1") (pinfunction "1_1") (pintype "passive"))
    )
    (net (code "38") (name "Net-(CHARGER-~{PG})") (class "Default")
      (node (ref "CHARGER") (pin "8") (pinfunction "~{PG}_8") (pintype "bidirectional"))
      (node (ref "LED3") (pin "C") (pinfunction "C_C") (pintype "passive"))
    )
    (net (code "39") (name "Net-(ENCODER1C-S)") (class "Default")
      (node (ref "ENCODER1") (pin "3") (pinfunction "S_3") (pintype "passive"))
      (node (ref "U$1") (pin "P$8") (pinfunction "1A4_P$8") (pintype "bidirectional"))
    )
    (net (code "40") (name "Net-(ENCODER1D-S)") (class "Default")
      (node (ref "ENCODER1") (pin "4") (pinfunction "S_4") (pintype "passive"))
      (node (ref "U$1") (pin "P$6") (pinfunction "1A3_P$6") (pintype "bidirectional"))
    )
    (net (code "41") (name "Net-(ENCODER2C-S)") (class "Default")
      (node (ref "ENCODER2") (pin "3") (pinfunction "S_3") (pintype "passive"))
      (node (ref "U$1") (pin "P$4") (pinfunction "1A2_P$4") (pintype "bidirectional"))
    )
    (net (code "42") (name "Net-(ENCODER2D-S)") (class "Default")
      (node (ref "ENCODER2") (pin "4") (pinfunction "S_4") (pintype "passive"))
      (node (ref "U$1") (pin "P$2") (pinfunction "1A1_P$2") (pintype "bidirectional"))
    )
    (net (code "43") (name "Net-(ENCODER3C-S)") (class "Default")
      (node (ref "ENCODER3") (pin "3") (pinfunction "S_3") (pintype "passive"))
      (node (ref "R1") (pin "1") (pinfunction "1_1") (pintype "passive"))
      (node (ref "U$1") (pin "P$17") (pinfunction "2A4_P$17") (pintype "bidirectional"))
    )
    (net (code "44") (name "Net-(ENCODER3D-S)") (class "Default")
      (node (ref "ENCODER3") (pin "4") (pinfunction "S_4") (pintype "passive"))
      (node (ref "R2") (pin "1") (pinfunction "1_1") (pintype "passive"))
      (node (ref "U$1") (pin "P$15") (pinfunction "2A3_P$15") (pintype "bidirectional"))
    )
    (net (code "45") (name "Net-(ENCODER4C-S)") (class "Default")
      (node (ref "ENCODER4") (pin "3") (pinfunction "S_3") (pintype "passive"))
      (node (ref "R8") (pin "1") (pinfunction "1_1") (pintype "passive"))
      (node (ref "U$1") (pin "P$13") (pinfunction "2A2_P$13") (pintype "bidirectional"))
    )
    (net (code "46") (name "Net-(ENCODER4D-S)") (class "Default")
      (node (ref "ENCODER4") (pin "4") (pinfunction "S_4") (pintype "passive"))
      (node (ref "R7") (pin "1") (pinfunction "1_1") (pintype "passive"))
      (node (ref "U$1") (pin "P$11") (pinfunction "2A1_P$11") (pintype "bidirectional"))
    )
    (net (code "47") (name "Net-(GAUGE-BAT)") (class "Default")
      (node (ref "GAUGE") (pin "4") (pinfunction "BAT_4") (pintype "bidirectional"))
      (node (ref "R50") (pin "2") (pinfunction "2_2") (pintype "passive"))
      (node (ref "R51") (pin "1") (pinfunction "1_1") (pintype "passive"))
    )
    (net (code "48") (name "Net-(GAUGE-CE)") (class "Default")
      (node (ref "C29") (pin "2") (pinfunction "2_2") (pintype "passive"))
      (node (ref "C30") (pin "2") (pinfunction "2_2") (pintype "passive"))
      (node (ref "C51") (pin "1") (pinfunction "1_1") (pintype "passive"))
      (node (ref "GAUGE") (pin "5") (pinfunction "CE_5") (pintype "bidirectional"))
      (node (ref "GAUGE") (pin "6") (pinfunction "REGIN_6") (pintype "bidirectional"))
      (node (ref "IC4") (pin "14") (pinfunction "VCC_14") (pintype "power_in"))
      (node (ref "IC4") (pin "9") (pinfunction "CLR_9") (pintype "input"))
      (node (ref "R31") (pin "2") (pinfunction "2_2") (pintype "passive"))
      (node (ref "R32") (pin "2") (pinfunction "2_2") (pintype "passive"))
      (node (ref "R33") (pin "2") (pinfunction "2_2") (pintype "passive"))
      (node (ref "R34") (pin "2") (pinfunction "2_2") (pintype "passive"))
      (node (ref "R35") (pin "2") (pinfunction "2_2") (pintype "passive"))
      (node (ref "R40") (pin "2") (pinfunction "2_2") (pintype "passive"))
      (node (ref "R41") (pin "2") (pinfunction "2_2") (pintype "passive"))
      (node (ref "R42") (pin "2") (pinfunction "2_2") (pintype "passive"))
      (node (ref "U$2") (pin "3") (pinfunction "OUT_3") (pintype "passive"))
    )
    (net (code "49") (name "Net-(GAUGE-P1)") (class "Default")
      (node (ref "GAUGE") (pin "3") (pinfunction "P1_3") (pintype "bidirectional"))
      (node (ref "IC4") (pin "1") (pinfunction "A_1") (pintype "input"))
      (node (ref "IC4") (pin "2") (pinfunction "B_2") (pintype "input"))
    )
    (net (code "50") (name "Net-(GAUGE-P2)") (class "Default")
      (node (ref "GAUGE") (pin "1") (pinfunction "P2_1") (pintype "bidirectional"))
      (node (ref "IC4") (pin "8") (pinfunction "CLK_8") (pintype "input"))
    )
    (net (code "51") (name "Net-(GAUGE-P3{slash}SDA)") (class "Default")
      (node (ref "GAUGE") (pin "8") (pinfunction "P3/SDA_8") (pintype "bidirectional"))
      (node (ref "I2C_SELECT") (pin "2") (pinfunction "2_2") (pintype "passive"))
    )
    (net (code "52") (name "Net-(GAUGE-P4{slash}SCL)") (class "Default")
      (node (ref "GAUGE") (pin "9") (pinfunction "P4/SCL_9") (pintype "bidirectional"))
      (node (ref "I2C_PGM") (pin "1") (pinfunction "S_1") (pintype "passive"))
      (node (ref "PROTECTION") (pin "27") (pinfunction "SCLK_27") (pintype "bidirectional"))
      (node (ref "R30") (pin "2") (pinfunction "2_2") (pintype "passive"))
    )
    (net (code "53") (name "Net-(GAUGE-REG25)") (class "Default")
      (node (ref "C33") (pin "1") (pinfunction "1_1") (pintype "passive"))
      (node (ref "GAUGE") (pin "7") (pinfunction "REG25_7") (pintype "bidirectional"))
      (node (ref "R49") (pin "1") (pinfunction "1_1") (pintype "passive"))
    )
    (net (code "54") (name "Net-(GAUGE-SRN)") (class "Default")
      (node (ref "C31") (pin "2") (pinfunction "2_2") (pintype "passive"))
      (node (ref "GAUGE") (pin "12") (pinfunction "SRN_12") (pintype "bidirectional"))
      (node (ref "R48") (pin "1") (pinfunction "1_1") (pintype "passive"))
    )
    (net (code "55") (name "Net-(GAUGE-SRP)") (class "Default")
      (node (ref "C32") (pin "2") (pinfunction "2_2") (pintype "passive"))
      (node (ref "GAUGE") (pin "13") (pinfunction "SRP_13") (pintype "bidirectional"))
      (node (ref "R47") (pin "1") (pinfunction "1_1") (pintype "passive"))
    )
    (net (code "56") (name "Net-(GAUGE-VEN)") (class "Default")
      (node (ref "GAUGE") (pin "2") (pinfunction "VEN_2") (pintype "bidirectional"))
      (node (ref "VIEW_SOC") (pin "P$3") (pinfunction "P$2_P$3") (pintype "bidirectional"))
      (node (ref "VIEW_SOC") (pin "P$4") (pinfunction "P$2_P$4") (pintype "bidirectional"))
    )
    (net (code "57") (name "Net-(I2C_PGMB-S)") (class "Default")
      (node (ref "I2C_PGM") (pin "2") (pinfunction "S_2") (pintype "passive"))
      (node (ref "I2C_SELECT") (pin "1") (pinfunction "1_1") (pintype "passive"))
      (node (ref "R29") (pin "2") (pinfunction "2_2") (pintype "passive"))
    )
    (net (code "58") (name "Net-(IC4A-QA)") (class "Default")
      (node (ref "IC4") (pin "3") (pinfunction "QA_3") (pintype "output"))
      (node (ref "SOC_LED1") (pin "C") (pinfunction "C_C") (pintype "passive"))
    )
    (net (code "59") (name "Net-(IC4A-QB)") (class "Default")
      (node (ref "IC4") (pin "4") (pinfunction "QB_4") (pintype "output"))
      (node (ref "SOC_LED2") (pin "C") (pinfunction "C_C") (pintype "passive"))
    )
    (net (code "60") (name "Net-(IC4A-QC)") (class "Default")
      (node (ref "IC4") (pin "5") (pinfunction "QC_5") (pintype "output"))
      (node (ref "SOC_LED3") (pin "C") (pinfunction "C_C") (pintype "passive"))
    )
    (net (code "61") (name "Net-(IC4A-QD)") (class "Default")
      (node (ref "IC4") (pin "6") (pinfunction "QD_6") (pintype "output"))
      (node (ref "SOC_LED4") (pin "C") (pinfunction "C_C") (pintype "passive"))
    )
    (net (code "62") (name "Net-(IC4A-QE)") (class "Default")
      (node (ref "IC4") (pin "10") (pinfunction "QE_10") (pintype "output"))
      (node (ref "SOC_LED5") (pin "C") (pinfunction "C_C") (pintype "passive"))
    )
    (net (code "63") (name "Net-(IC4A-QF)") (class "Default")
      (node (ref "IC4") (pin "11") (pinfunction "QF_11") (pintype "output"))
      (node (ref "SOC_LED6") (pin "C") (pinfunction "C_C") (pintype "passive"))
    )
    (net (code "64") (name "Net-(IC4A-QG)") (class "Default")
      (node (ref "IC4") (pin "12") (pinfunction "QG_12") (pintype "output"))
      (node (ref "SOC_LED7") (pin "C") (pinfunction "C_C") (pintype "passive"))
    )
    (net (code "65") (name "Net-(IC4A-QH)") (class "Default")
      (node (ref "IC4") (pin "13") (pinfunction "QH_13") (pintype "output"))
      (node (ref "SOC_LED8") (pin "C") (pinfunction "C_C") (pintype "passive"))
    )
    (net (code "66") (name "Net-(LED1-PadA)") (class "Default")
      (node (ref "LED1") (pin "A") (pinfunction "A_A") (pintype "passive"))
      (node (ref "R10") (pin "1") (pinfunction "1_1") (pintype "passive"))
    )
    (net (code "67") (name "Net-(LED2-PadA)") (class "Default")
      (node (ref "LED2") (pin "A") (pinfunction "A_A") (pintype "passive"))
      (node (ref "R13") (pin "1") (pinfunction "1_1") (pintype "passive"))
    )
    (net (code "68") (name "Net-(LED3-PadA)") (class "Default")
      (node (ref "LED3") (pin "A") (pinfunction "A_A") (pintype "passive"))
      (node (ref "R14") (pin "1") (pinfunction "1_1") (pintype "passive"))
    )
    (net (code "69") (name "Net-(PGM_PWRB-S)") (class "Default")
      (node (ref "PGM_PWR") (pin "2") (pinfunction "S_2") (pintype "passive"))
      (node (ref "PROTECTION") (pin "28") (pinfunction "EEPROM_28") (pintype "bidirectional"))
    )
    (net (code "70") (name "Net-(PROTECTION-BAT)") (class "Default")
      (node (ref "C34") (pin "1") (pinfunction "1_1") (pintype "passive"))
      (node (ref "C36") (pin "1") (pinfunction "1_1") (pintype "passive"))
      (node (ref "D2") (pin "C") (pinfunction "C_C") (pintype "passive"))
      (node (ref "PROTECTION") (pin "31") (pinfunction "BAT_31") (pintype "bidirectional"))
    )
    (net (code "71") (name "Net-(PROTECTION-CCAP)") (class "Default")
      (node (ref "CCCAP") (pin "2") (pinfunction "2_2") (pintype "passive"))
      (node (ref "PROTECTION") (pin "20") (pinfunction "CCAP_20") (pintype "bidirectional"))
    )
    (net (code "72") (name "Net-(PROTECTION-CHG)") (class "Default")
      (node (ref "PROTECTION") (pin "21") (pinfunction "CHG_21") (pintype "bidirectional"))
      (node (ref "Q8") (pin "1") (pinfunction "G_1") (pintype "passive"))
      (node (ref "R37") (pin "2") (pinfunction "2_2") (pintype "passive"))
    )
    (net (code "73") (name "Net-(PROTECTION-CPCKN)") (class "Default")
      (node (ref "PROTECTION") (pin "19") (pinfunction "CPCKN_19") (pintype "bidirectional"))
      (node (ref "RCPCKN") (pin "2") (pinfunction "2_2") (pintype "passive"))
    )
    (net (code "74") (name "Net-(PROTECTION-DCAP)") (class "Default")
      (node (ref "CDCAP") (pin "2") (pinfunction "2_2") (pintype "passive"))
      (node (ref "PROTECTION") (pin "16") (pinfunction "DCAP_16") (pintype "bidirectional"))
    )
    (net (code "75") (name "Net-(PROTECTION-DPCKN)") (class "Default")
      (node (ref "PROTECTION") (pin "18") (pinfunction "DPCKN_18") (pintype "bidirectional"))
      (node (ref "RDPCKN") (pin "2") (pinfunction "2_2") (pintype "passive"))
      (node (ref "RLDRM_DET") (pin "1") (pinfunction "1_1") (pintype "passive"))
    )
    (net (code "76") (name "Net-(PROTECTION-DSG)") (class "Default")
      (node (ref "PROTECTION") (pin "17") (pinfunction "DSG_17") (pintype "bidirectional"))
      (node (ref "R39") (pin "2") (pinfunction "2_2") (pintype "passive"))
    )
    (net (code "77") (name "Net-(PROTECTION-SDATA)") (class "Default")
      (node (ref "I2C_SELECT") (pin "3") (pinfunction "3_3") (pintype "passive"))
      (node (ref "PROTECTION") (pin "26") (pinfunction "SDATA_26") (pintype "bidirectional"))
    )
    (net (code "78") (name "Net-(PROTECTION-SENSE+)") (class "Default")
      (node (ref "C39") (pin "2") (pinfunction "2_2") (pintype "passive"))
      (node (ref "PROTECTION") (pin "10") (pinfunction "SENSE+_10") (pintype "bidirectional"))
      (node (ref "R45") (pin "1") (pinfunction "1_1") (pintype "passive"))
    )
    (net (code "79") (name "Net-(PROTECTION-SENSE-)") (class "Default")
      (node (ref "C40") (pin "2") (pinfunction "2_2") (pintype "passive"))
      (node (ref "PROTECTION") (pin "9") (pinfunction "SENSE-_9") (pintype "bidirectional"))
      (node (ref "R44") (pin "1") (pinfunction "1_1") (pintype "passive"))
    )
    (net (code "80") (name "Net-(PROTECTION-VC1)") (class "Default")
      (node (ref "PROTECTION") (pin "34") (pinfunction "VC1_34") (pintype "bidirectional"))
      (node (ref "R36") (pin "1") (pinfunction "1_1") (pintype "passive"))
    )
    (net (code "81") (name "Net-(PROTECTION-VC2)") (class "Default")
      (node (ref "CVC2") (pin "1") (pinfunction "1_1") (pintype "passive"))
      (node (ref "PROTECTION") (pin "36") (pinfunction "VC2_36") (pintype "bidirectional"))
      (node (ref "R36") (pin "2") (pinfunction "2_2") (pintype "passive"))
      (node (ref "RVC2") (pin "1") (pinfunction "1_1") (pintype "passive"))
    )
    (net (code "82") (name "Net-(PROTECTION-VC3)") (class "Default")
      (node (ref "CVC2") (pin "2") (pinfunction "2_2") (pintype "passive"))
      (node (ref "CVC3") (pin "1") (pinfunction "1_1") (pintype "passive"))
      (node (ref "PROTECTION") (pin "38") (pinfunction "VC3_38") (pintype "bidirectional"))
      (node (ref "RVC3") (pin "1") (pinfunction "1_1") (pintype "passive"))
    )
    (net (code "83") (name "Net-(PROTECTION-VC4)") (class "Default")
      (node (ref "CVC3") (pin "2") (pinfunction "2_2") (pintype "passive"))
      (node (ref "CVC4") (pin "1") (pinfunction "1_1") (pintype "passive"))
      (node (ref "PROTECTION") (pin "1") (pinfunction "VC4_1") (pintype "bidirectional"))
      (node (ref "RVC4") (pin "1") (pinfunction "1_1") (pintype "passive"))
    )
    (net (code "84") (name "Net-(PROTECTION-VC5)") (class "Default")
      (node (ref "CVC4") (pin "2") (pinfunction "2_2") (pintype "passive"))
      (node (ref "CVC5") (pin "1") (pinfunction "1_1") (pintype "passive"))
      (node (ref "PROTECTION") (pin "3") (pinfunction "VC5_3") (pintype "bidirectional"))
      (node (ref "RVC5") (pin "1") (pinfunction "1_1") (pintype "passive"))
    )
    (net (code "85") (name "Net-(PROTECTION-VC6)") (class "Default")
      (node (ref "CVC5") (pin "2") (pinfunction "2_2") (pintype "passive"))
      (node (ref "CVC6") (pin "1") (pinfunction "1_1") (pintype "passive"))
      (node (ref "PROTECTION") (pin "5") (pinfunction "VC6_5") (pintype "bidirectional"))
      (node (ref "RVC6") (pin "1") (pinfunction "1_1") (pintype "passive"))
    )
    (net (code "86") (name "Net-(PROTECTION-VC7)") (class "Default")
      (node (ref "CVC6") (pin "2") (pinfunction "2_2") (pintype "passive"))
      (node (ref "CVC7") (pin "1") (pinfunction "1_1") (pintype "passive"))
      (node (ref "PROTECTION") (pin "6") (pinfunction "VC7_6") (pintype "bidirectional"))
      (node (ref "RVC7") (pin "1") (pinfunction "1_1") (pintype "passive"))
    )
    (net (code "87") (name "Net-(PROTECTION-VC8)") (class "Default")
      (node (ref "CVC7") (pin "2") (pinfunction "2_2") (pintype "passive"))
      (node (ref "CVC8") (pin "1") (pinfunction "1_1") (pintype "passive"))
      (node (ref "PROTECTION") (pin "7") (pinfunction "VC8_7") (pintype "bidirectional"))
      (node (ref "RVC8") (pin "1") (pinfunction "1_1") (pintype "passive"))
    )
    (net (code "88") (name "Net-(PROTECTION-VC9)") (class "Default")
      (node (ref "CVC8") (pin "2") (pinfunction "2_2") (pintype "passive"))
      (node (ref "PROTECTION") (pin "8") (pinfunction "VC9_8") (pintype "bidirectional"))
      (node (ref "RVC9") (pin "1") (pinfunction "1_1") (pintype "passive"))
    )
    (net (code "89") (name "Net-(PROTECTION-VREG)") (class "Default")
      (node (ref "CVREG") (pin "2") (pinfunction "2_2") (pintype "passive"))
      (node (ref "PGM_ENABLE") (pin "1") (pinfunction "1_1") (pintype "passive"))
      (node (ref "PROTECTION") (pin "12") (pinfunction "VREG_12") (pintype "bidirectional"))
      (node (ref "R29") (pin "1") (pinfunction "1_1") (pintype "passive"))
      (node (ref "R30") (pin "1") (pinfunction "1_1") (pintype "passive"))
    )
    (net (code "90") (name "Net-(PROTECTION-ZEDE)") (class "Default")
      (node (ref "PGM_ENABLE") (pin "2") (pinfunction "2_2") (pintype "passive"))
      (node (ref "PROTECTION") (pin "22") (pinfunction "ZEDE_22") (pintype "bidirectional"))
    )
    (net (code "91") (name "Net-(Q3-G)") (class "Default")
      (node (ref "C12") (pin "2") (pinfunction "2_2") (pintype "passive"))
      (node (ref "Q3") (pin "1") (pinfunction "G_1") (pintype "passive"))
      (node (ref "Q4") (pin "1") (pinfunction "G_1") (pintype "passive"))
      (node (ref "R4") (pin "1") (pinfunction "1_1") (pintype "passive"))
      (node (ref "R5") (pin "2") (pinfunction "2_2") (pintype "passive"))
    )
    (net (code "92") (name "Net-(Q3-S)") (class "Default")
      (node (ref "C12") (pin "1") (pinfunction "1_1") (pintype "passive"))
      (node (ref "Q3") (pin "2") (pinfunction "S_2") (pintype "passive"))
      (node (ref "Q4") (pin "2") (pinfunction "S_2") (pintype "passive"))
      (node (ref "R4") (pin "2") (pinfunction "2_2") (pintype "passive"))
      (node (ref "R9") (pin "2") (pinfunction "2_2") (pintype "passive"))
    )
    (net (code "93") (name "Net-(Q5-G)") (class "Default")
      (node (ref "C21") (pin "2") (pinfunction "2_2") (pintype "passive"))
      (node (ref "Q5") (pin "1") (pinfunction "G_1") (pintype "passive"))
      (node (ref "R23") (pin "2") (pinfunction "2_2") (pintype "passive"))
      (node (ref "R24") (pin "2") (pinfunction "2_2") (pintype "passive"))
    )
    (net (code "94") (name "Net-(Q8-D)") (class "Default")
      (node (ref "Q8") (pin "3") (pinfunction "D_3") (pintype "passive"))
      (node (ref "Q9") (pin "3") (pinfunction "D_3") (pintype "passive"))
      (node (ref "RDPCKN") (pin "1") (pinfunction "1_1") (pintype "passive"))
    )
    (net (code "95") (name "Net-(Q9-G)") (class "Default")
      (node (ref "Q9") (pin "1") (pinfunction "G_1") (pintype "passive"))
      (node (ref "R38") (pin "2") (pinfunction "2_2") (pintype "passive"))
      (node (ref "R39") (pin "1") (pinfunction "1_1") (pintype "passive"))
    )
    (net (code "96") (name "Net-(Q9-S)") (class "Default")
      (node (ref "Q9") (pin "2") (pinfunction "S_2") (pintype "passive"))
      (node (ref "R38") (pin "1") (pinfunction "1_1") (pintype "passive"))
      (node (ref "R43") (pin "1") (pinfunction "1_1") (pintype "passive"))
      (node (ref "R47") (pin "2") (pinfunction "2_2") (pintype "passive"))
    )
    (net (code "97") (name "Net-(QG1-OUT)") (class "Default")
      (node (ref "P4") (pin "14") (pinfunction "14_14") (pintype "passive"))
      (node (ref "QG1") (pin "3") (pinfunction "OUT_3") (pintype "output"))
    )
    (net (code "98") (name "Net-(R31-Pad1)") (class "Default")
      (node (ref "R31") (pin "1") (pinfunction "1_1") (pintype "passive"))
      (node (ref "SOC_LED1") (pin "A") (pinfunction "A_A") (pintype "passive"))
    )
    (net (code "99") (name "Net-(R32-Pad1)") (class "Default")
      (node (ref "R32") (pin "1") (pinfunction "1_1") (pintype "passive"))
      (node (ref "SOC_LED2") (pin "A") (pinfunction "A_A") (pintype "passive"))
    )
    (net (code "100") (name "Net-(R33-Pad1)") (class "Default")
      (node (ref "R33") (pin "1") (pinfunction "1_1") (pintype "passive"))
      (node (ref "SOC_LED3") (pin "A") (pinfunction "A_A") (pintype "passive"))
    )
    (net (code "101") (name "Net-(R34-Pad1)") (class "Default")
      (node (ref "R34") (pin "1") (pinfunction "1_1") (pintype "passive"))
      (node (ref "SOC_LED4") (pin "A") (pinfunction "A_A") (pintype "passive"))
    )
    (net (code "102") (name "Net-(R35-Pad1)") (class "Default")
      (node (ref "R35") (pin "1") (pinfunction "1_1") (pintype "passive"))
      (node (ref "SOC_LED5") (pin "A") (pinfunction "A_A") (pintype "passive"))
    )
    (net (code "103") (name "Net-(R40-Pad1)") (class "Default")
      (node (ref "R40") (pin "1") (pinfunction "1_1") (pintype "passive"))
      (node (ref "SOC_LED6") (pin "A") (pinfunction "A_A") (pintype "passive"))
    )
    (net (code "104") (name "Net-(R41-Pad1)") (class "Default")
      (node (ref "R41") (pin "1") (pinfunction "1_1") (pintype "passive"))
      (node (ref "SOC_LED7") (pin "A") (pinfunction "A_A") (pintype "passive"))
    )
    (net (code "105") (name "Net-(R42-Pad1)") (class "Default")
      (node (ref "R42") (pin "1") (pinfunction "1_1") (pintype "passive"))
      (node (ref "SOC_LED8") (pin "A") (pinfunction "A_A") (pintype "passive"))
    )
    (net (code "106") (name "Net-(R43-Pad2)") (class "Default")
      (node (ref "R43") (pin "2") (pinfunction "2_2") (pintype "passive"))
      (node (ref "R45") (pin "2") (pinfunction "2_2") (pintype "passive"))
      (node (ref "R46") (pin "1") (pinfunction "1_1") (pintype "passive"))
      (node (ref "R48") (pin "2") (pinfunction "2_2") (pintype "passive"))
    )
    (net (code "107") (name "Net-(R49-Pad2)") (class "Default")
      (node (ref "R49") (pin "2") (pinfunction "2_2") (pintype "passive"))
      (node (ref "VIEW_SOC") (pin "P$1") (pinfunction "P$1_P$1") (pintype "bidirectional"))
      (node (ref "VIEW_SOC") (pin "P$2") (pinfunction "P$1_P$2") (pintype "bidirectional"))
    )
    (net (code "108") (name "Net-(U$1-1Y1)") (class "Default")
      (node (ref "P4") (pin "15") (pinfunction "15_15") (pintype "passive"))
      (node (ref "U$1") (pin "P$18") (pinfunction "1Y1_P$18") (pintype "bidirectional"))
    )
    (net (code "109") (name "Net-(U$1-1Y2)") (class "Default")
      (node (ref "P4") (pin "21") (pinfunction "21_21") (pintype "passive"))
      (node (ref "U$1") (pin "P$16") (pinfunction "1Y2_P$16") (pintype "bidirectional"))
    )
    (net (code "110") (name "Net-(U$1-1Y3)") (class "Default")
      (node (ref "P4") (pin "22") (pinfunction "22_22") (pintype "passive"))
      (node (ref "U$1") (pin "P$14") (pinfunction "1Y3_P$14") (pintype "bidirectional"))
    )
    (net (code "111") (name "Net-(U$1-1Y4)") (class "Default")
      (node (ref "P4") (pin "23") (pinfunction "23_23") (pintype "passive"))
      (node (ref "U$1") (pin "P$12") (pinfunction "1Y4_P$12") (pintype "bidirectional"))
    )
    (net (code "112") (name "Net-(U$1-2Y1)") (class "Default")
      (node (ref "P1") (pin "1") (pinfunction "1_1") (pintype "passive"))
      (node (ref "U$1") (pin "P$9") (pinfunction "2Y1_P$9") (pintype "bidirectional"))
    )
    (net (code "113") (name "Net-(U$1-2Y2)") (class "Default")
      (node (ref "P1") (pin "2") (pinfunction "2_2") (pintype "passive"))
      (node (ref "U$1") (pin "P$7") (pinfunction "2Y2_P$7") (pintype "bidirectional"))
    )
    (net (code "114") (name "Net-(U$1-2Y3)") (class "Default")
      (node (ref "P1") (pin "3") (pinfunction "3_3") (pintype "passive"))
      (node (ref "U$1") (pin "P$5") (pinfunction "2Y3_P$5") (pintype "bidirectional"))
    )
    (net (code "115") (name "Net-(U$1-2Y4)") (class "Default")
      (node (ref "P1") (pin "4") (pinfunction "4_4") (pintype "passive"))
      (node (ref "U$1") (pin "P$3") (pinfunction "2Y4_P$3") (pintype "bidirectional"))
    )
    (net (code "116") (name "unconnected-(GAUGE-P5{slash}HDQ-Pad10)") (class "Default")
      (node (ref "GAUGE") (pin "10") (pinfunction "P5/HDQ_10") (pintype "bidirectional"))
    )
    (net (code "117") (name "unconnected-(GAUGE-P6{slash}TS-Pad11)") (class "Default")
      (node (ref "GAUGE") (pin "11") (pinfunction "P6/TS_11") (pintype "bidirectional"))
    )
    (net (code "118") (name "unconnected-(P1-Pad5)") (class "Default")
      (node (ref "P1") (pin "5") (pinfunction "5_5") (pintype "passive"))
    )
    (net (code "119") (name "unconnected-(P1-Pad6)") (class "Default")
      (node (ref "P1") (pin "6") (pinfunction "6_6") (pintype "passive"))
    )
    (net (code "120") (name "unconnected-(P1-Pad7)") (class "Default")
      (node (ref "P1") (pin "7") (pinfunction "7_7") (pintype "passive"))
    )
    (net (code "121") (name "unconnected-(P1-Pad8)") (class "Default")
      (node (ref "P1") (pin "8") (pinfunction "8_8") (pintype "passive"))
    )
    (net (code "122") (name "unconnected-(P1-Pad9)") (class "Default")
      (node (ref "P1") (pin "9") (pinfunction "9_9") (pintype "passive"))
    )
    (net (code "123") (name "unconnected-(P1-Pad10)") (class "Default")
      (node (ref "P1") (pin "10") (pinfunction "10_10") (pintype "passive"))
    )
    (net (code "124") (name "unconnected-(P1-Pad11)") (class "Default")
      (node (ref "P1") (pin "11") (pinfunction "11_11") (pintype "passive"))
    )
    (net (code "125") (name "unconnected-(P1-Pad12)") (class "Default")
      (node (ref "P1") (pin "12") (pinfunction "12_12") (pintype "passive"))
    )
    (net (code "126") (name "unconnected-(P1-Pad13)") (class "Default")
      (node (ref "P1") (pin "13") (pinfunction "13_13") (pintype "passive"))
    )
    (net (code "127") (name "unconnected-(P1-Pad14)") (class "Default")
      (node (ref "P1") (pin "14") (pinfunction "14_14") (pintype "passive"))
    )
    (net (code "128") (name "unconnected-(P1-Pad15)") (class "Default")
      (node (ref "P1") (pin "15") (pinfunction "15_15") (pintype "passive"))
    )
    (net (code "129") (name "unconnected-(P1-Pad16)") (class "Default")
      (node (ref "P1") (pin "16") (pinfunction "16_16") (pintype "passive"))
    )
    (net (code "130") (name "unconnected-(P3-Pad1)") (class "Default")
      (node (ref "P3") (pin "1") (pinfunction "1_1") (pintype "passive"))
    )
    (net (code "131") (name "unconnected-(P3-Pad2)") (class "Default")
      (node (ref "P3") (pin "2") (pinfunction "2_2") (pintype "passive"))
    )
    (net (code "132") (name "unconnected-(P3-Pad3)") (class "Default")
      (node (ref "P3") (pin "3") (pinfunction "3_3") (pintype "passive"))
    )
    (net (code "133") (name "unconnected-(P3-Pad4)") (class "Default")
      (node (ref "P3") (pin "4") (pinfunction "4_4") (pintype "passive"))
    )
    (net (code "134") (name "unconnected-(P3-Pad5)") (class "Default")
      (node (ref "P3") (pin "5") (pinfunction "5_5") (pintype "passive"))
    )
    (net (code "135") (name "unconnected-(P3-Pad6)") (class "Default")
      (node (ref "P3") (pin "6") (pinfunction "6_6") (pintype "passive"))
    )
    (net (code "136") (name "unconnected-(P3-Pad7)") (class "Default")
      (node (ref "P3") (pin "7") (pinfunction "7_7") (pintype "passive"))
    )
    (net (code "137") (name "unconnected-(P3-Pad8)") (class "Default")
      (node (ref "P3") (pin "8") (pinfunction "8_8") (pintype "passive"))
    )
    (net (code "138") (name "unconnected-(P3-Pad9)") (class "Default")
      (node (ref "P3") (pin "9") (pinfunction "9_9") (pintype "passive"))
    )
    (net (code "139") (name "unconnected-(P3-Pad10)") (class "Default")
      (node (ref "P3") (pin "10") (pinfunction "10_10") (pintype "passive"))
    )
    (net (code "140") (name "unconnected-(P3-Pad11)") (class "Default")
      (node (ref "P3") (pin "11") (pinfunction "11_11") (pintype "passive"))
    )
    (net (code "141") (name "unconnected-(P3-Pad12)") (class "Default")
      (node (ref "P3") (pin "12") (pinfunction "12_12") (pintype "passive"))
    )
    (net (code "142") (name "unconnected-(P3-Pad13)") (class "Default")
      (node (ref "P3") (pin "13") (pinfunction "13_13") (pintype "passive"))
    )
    (net (code "143") (name "unconnected-(P3-Pad14)") (class "Default")
      (node (ref "P3") (pin "14") (pinfunction "14_14") (pintype "passive"))
    )
    (net (code "144") (name "unconnected-(P3-Pad15)") (class "Default")
      (node (ref "P3") (pin "15") (pinfunction "15_15") (pintype "passive"))
    )
    (net (code "145") (name "unconnected-(P3-Pad16)") (class "Default")
      (node (ref "P3") (pin "16") (pinfunction "16_16") (pintype "passive"))
    )
    (net (code "146") (name "unconnected-(P4-Pad3)") (class "Default")
      (node (ref "P4") (pin "3") (pinfunction "3_3") (pintype "passive"))
    )
    (net (code "147") (name "unconnected-(P4-Pad4)") (class "Default")
      (node (ref "P4") (pin "4") (pinfunction "4_4") (pintype "passive"))
    )
    (net (code "148") (name "unconnected-(P4-Pad5)") (class "Default")
      (node (ref "P4") (pin "5") (pinfunction "5_5") (pintype "passive"))
    )
    (net (code "149") (name "unconnected-(P4-Pad6)") (class "Default")
      (node (ref "P4") (pin "6") (pinfunction "6_6") (pintype "passive"))
    )
    (net (code "150") (name "unconnected-(P4-Pad7)") (class "Default")
      (node (ref "P4") (pin "7") (pinfunction "7_7") (pintype "passive"))
    )
    (net (code "151") (name "unconnected-(P4-Pad8)") (class "Default")
      (node (ref "P4") (pin "8") (pinfunction "8_8") (pintype "passive"))
    )
    (net (code "152") (name "unconnected-(P4-Pad9)") (class "Default")
      (node (ref "P4") (pin "9") (pinfunction "9_9") (pintype "passive"))
    )
    (net (code "153") (name "unconnected-(P4-Pad10)") (class "Default")
      (node (ref "P4") (pin "10") (pinfunction "10_10") (pintype "passive"))
    )
    (net (code "154") (name "unconnected-(P4-Pad11)") (class "Default")
      (node (ref "P4") (pin "11") (pinfunction "11_11") (pintype "passive"))
    )
    (net (code "155") (name "unconnected-(P4-Pad12)") (class "Default")
      (node (ref "P4") (pin "12") (pinfunction "12_12") (pintype "passive"))
    )
    (net (code "156") (name "unconnected-(P4-Pad13)") (class "Default")
      (node (ref "P4") (pin "13") (pinfunction "13_13") (pintype "passive"))
    )
    (net (code "157") (name "unconnected-(P4-Pad16)") (class "Default")
      (node (ref "P4") (pin "16") (pinfunction "16_16") (pintype "passive"))
    )
    (net (code "158") (name "unconnected-(P4-Pad17)") (class "Default")
      (node (ref "P4") (pin "17") (pinfunction "17_17") (pintype "passive"))
    )
    (net (code "159") (name "unconnected-(P4-Pad18)") (class "Default")
      (node (ref "P4") (pin "18") (pinfunction "18_18") (pintype "passive"))
    )
    (net (code "160") (name "unconnected-(P4-Pad19)") (class "Default")
      (node (ref "P4") (pin "19") (pinfunction "19_19") (pintype "passive"))
    )
    (net (code "161") (name "unconnected-(P4-Pad20)") (class "Default")
      (node (ref "P4") (pin "20") (pinfunction "20_20") (pintype "passive"))
    )
    (net (code "162") (name "unconnected-(P4-Pad24)") (class "Default")
      (node (ref "P4") (pin "24") (pinfunction "24_24") (pintype "passive"))
    )
    (net (code "163") (name "unconnected-(P4-Pad27)") (class "Default")
      (node (ref "P4") (pin "27") (pinfunction "27_27") (pintype "passive"))
    )
    (net (code "164") (name "unconnected-(PROTECTION-VTSB-Pad15)") (class "Default")
      (node (ref "PROTECTION") (pin "15") (pinfunction "VTSB_15") (pintype "bidirectional"))
    )
    (net (code "165") (name "unconnected-(QG1-E{slash}D-Pad1)") (class "Default")
      (node (ref "QG1") (pin "1") (pinfunction "E/D_1") (pintype "input"))
    )
  )
)
